# PCU.net
KiCad netlist of a schematic drawn in EAGLE
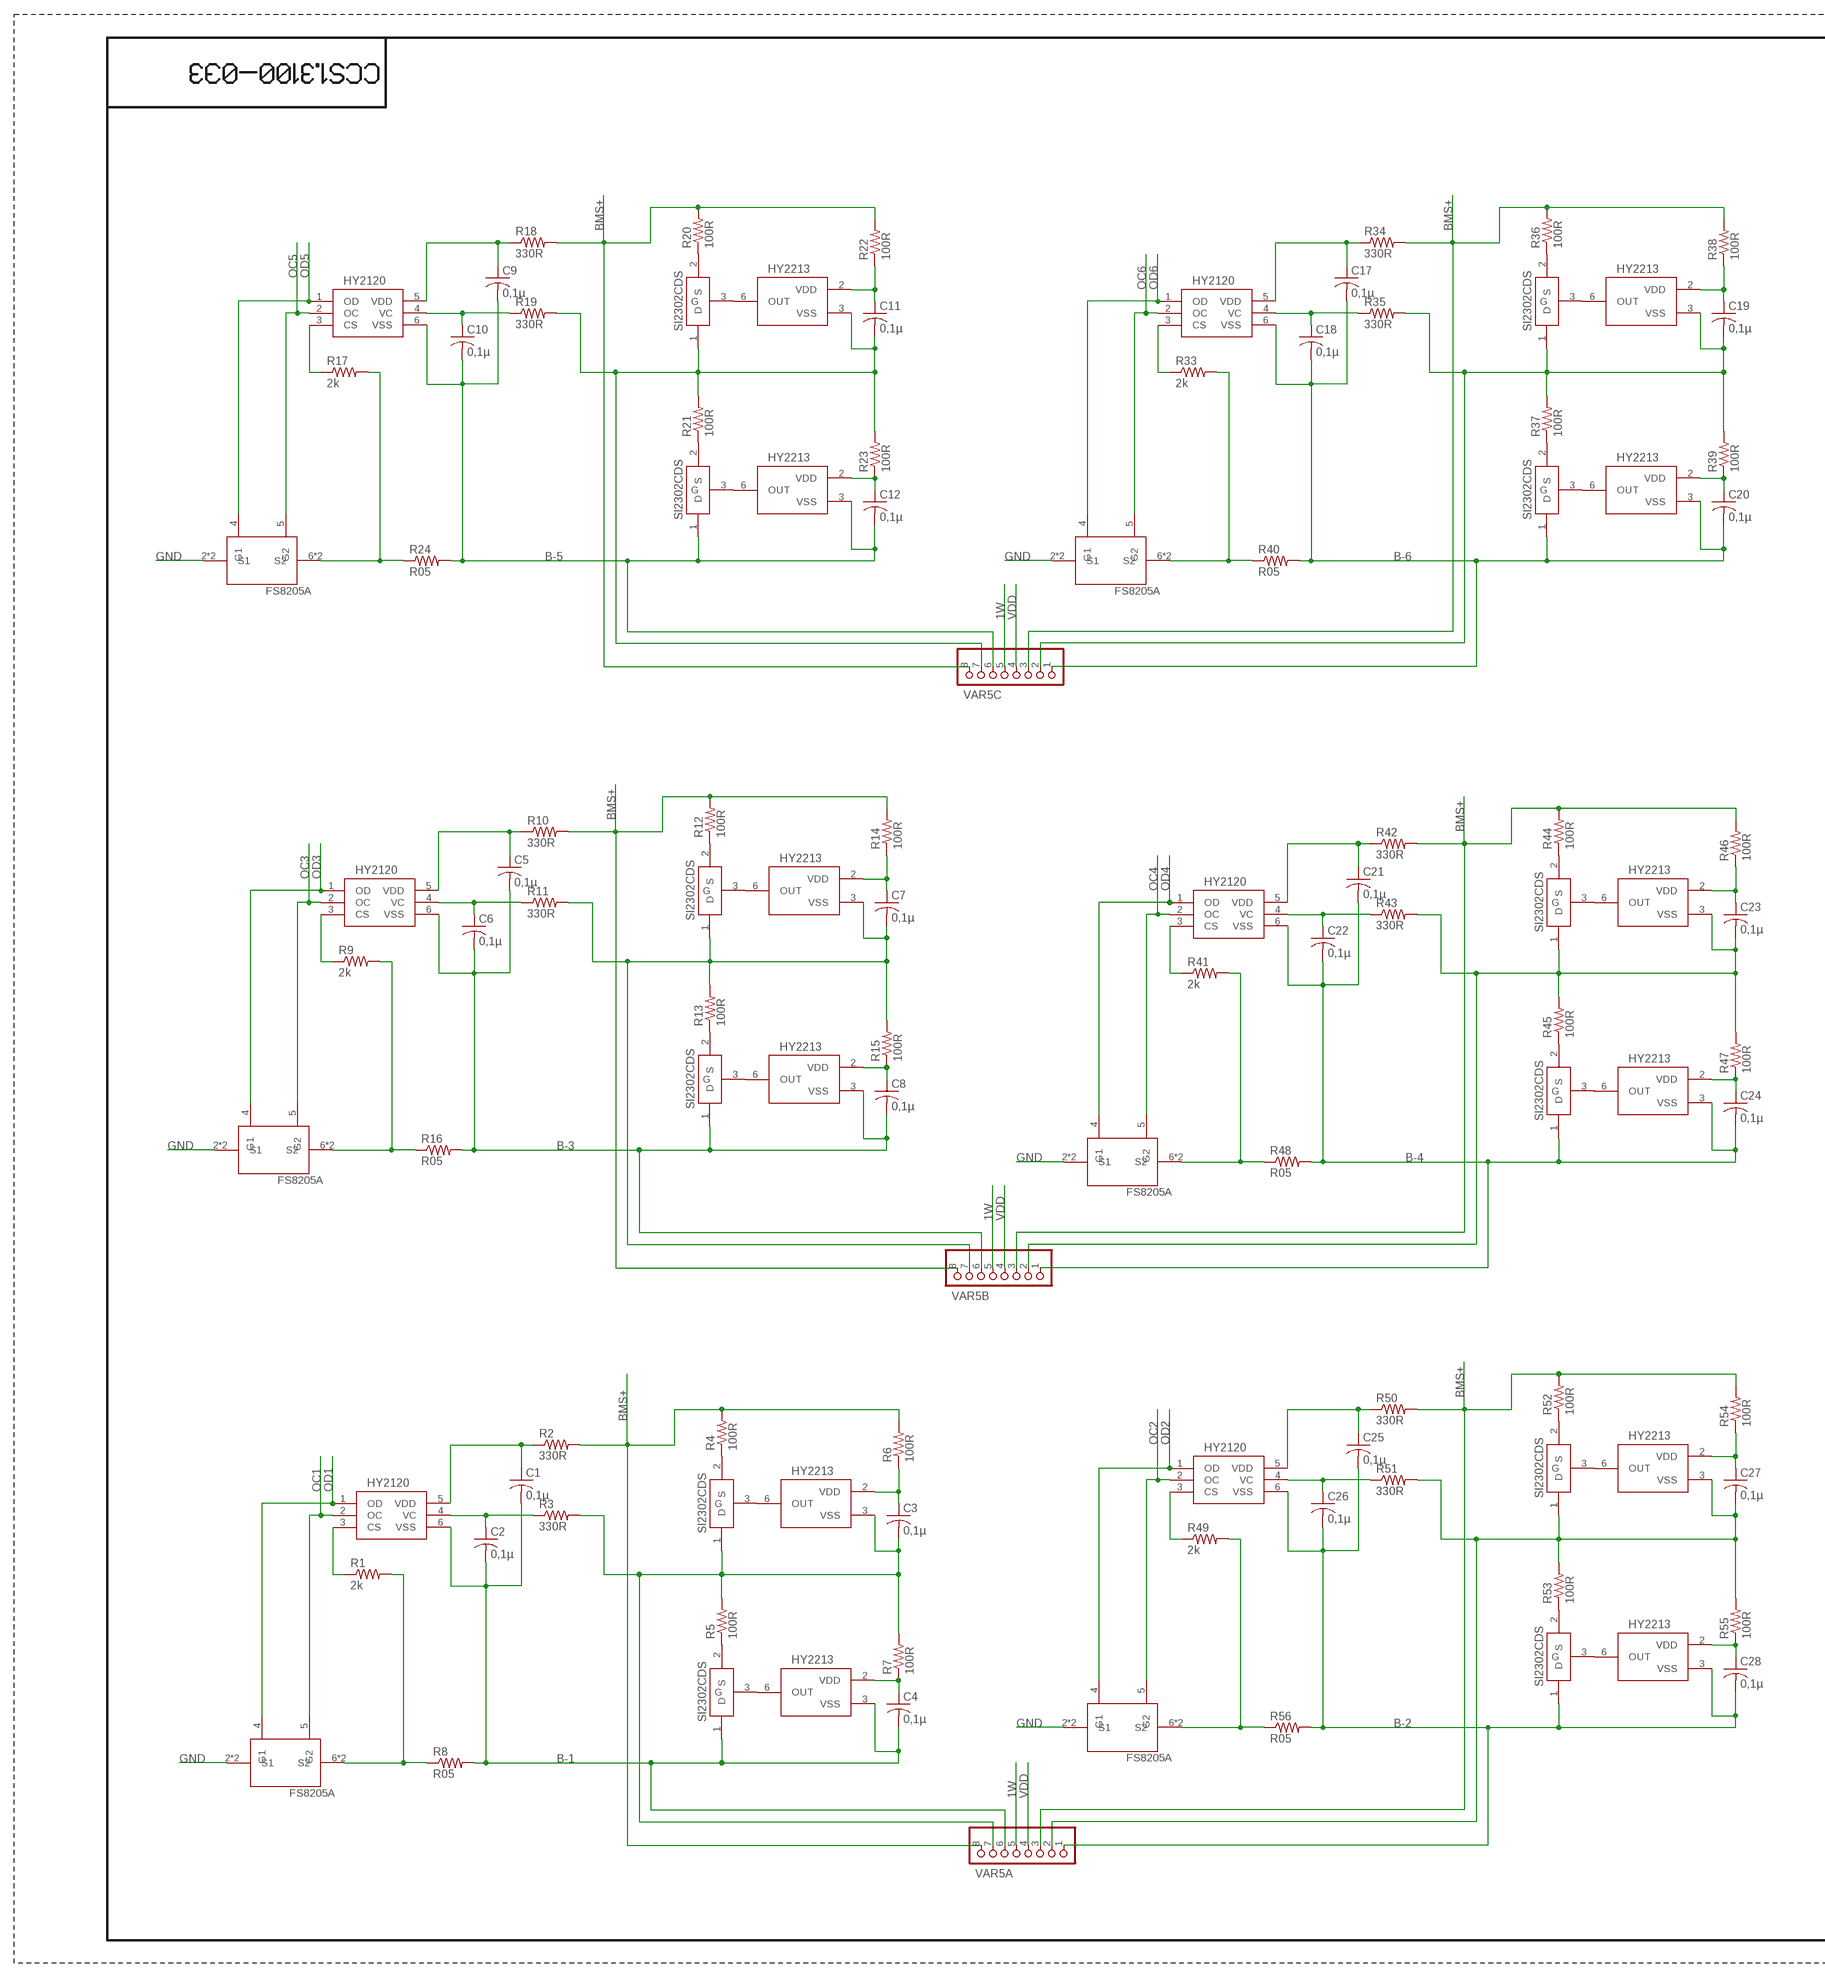
[diagram p0: schematic, sheet 1, part 1 of 2]
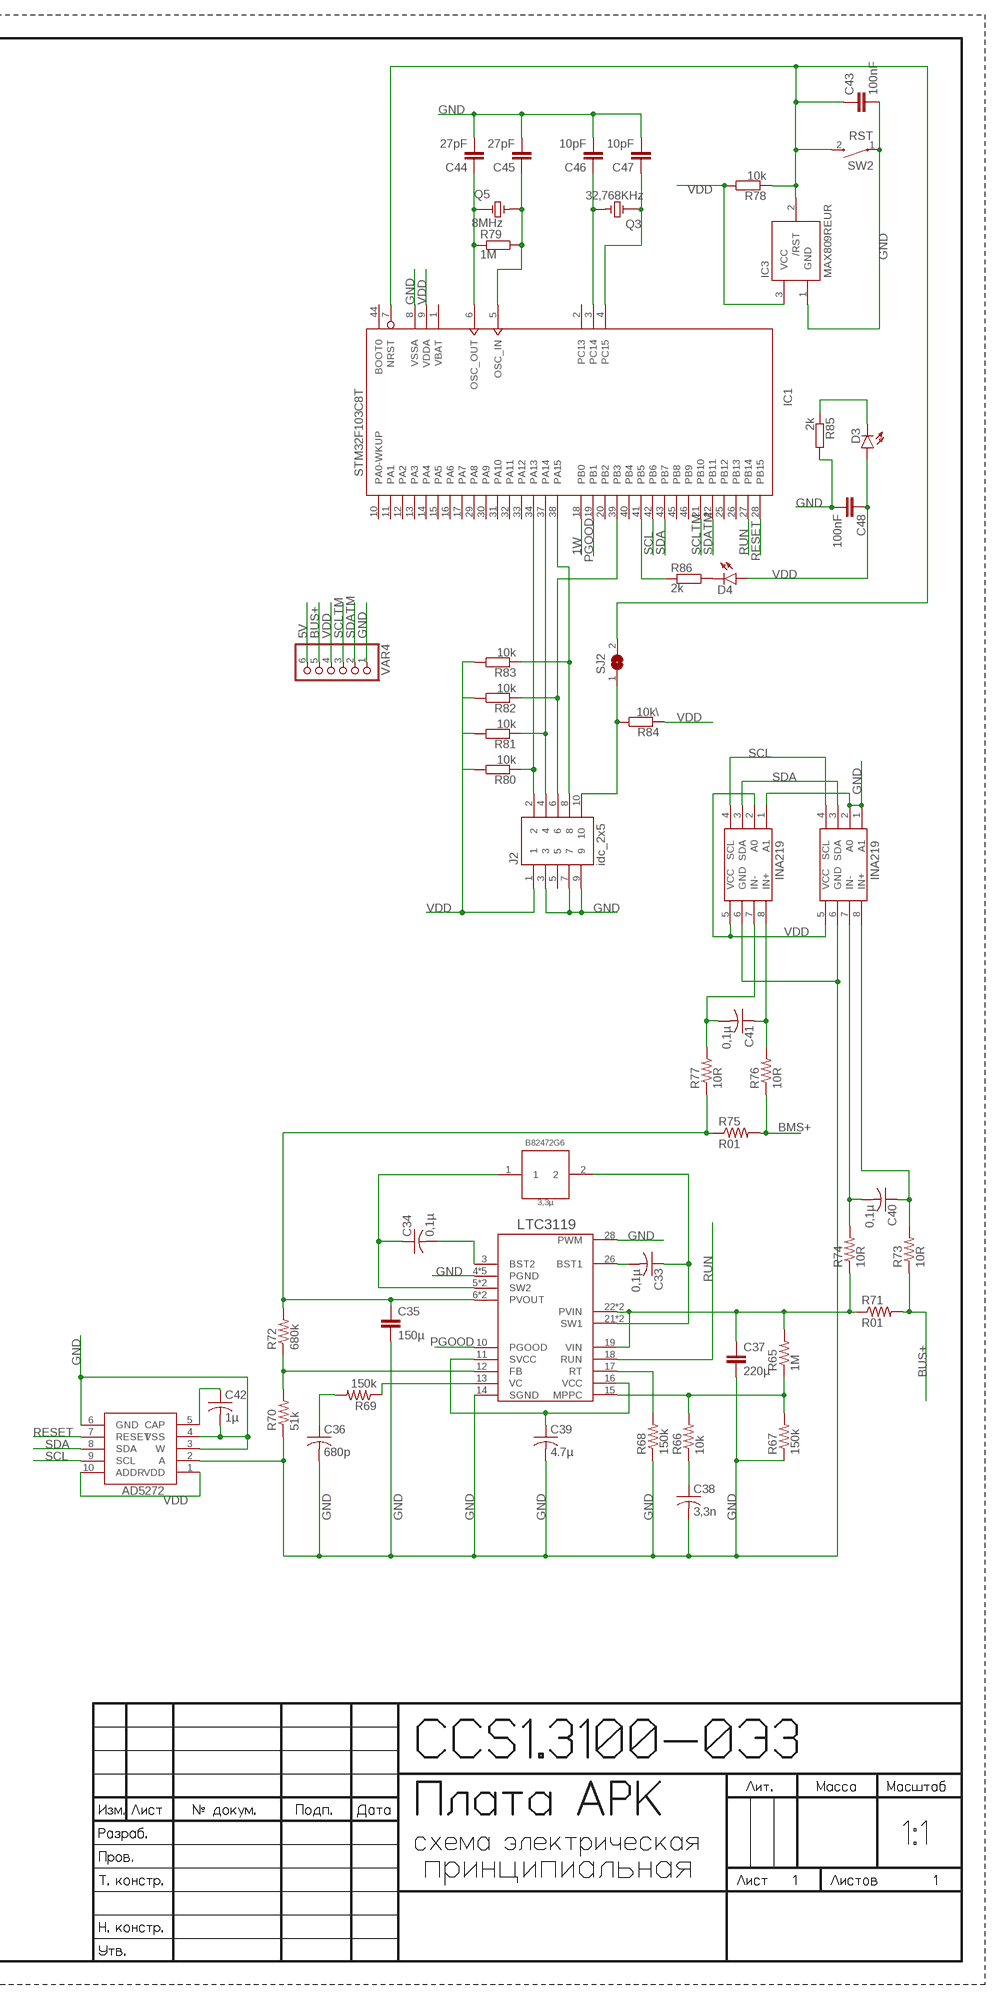
[diagram p1: schematic, sheet 1, part 2 of 2]

(export (version "E")
  (design (tool "Eeschema 10.0.6"))
  (components
    (comp (ref "3,3µH")
      (value "3,3µ")
      (footprint "eagle-import:B82472G6")
      (libsource (lib "eagle-import") (part "B82472G6"))
    )
    (comp (ref "C1")
      (value "0,1µ")
      (footprint "eagle-import:C0603")
      (libsource (lib "eagle-import") (part "C-USC0603"))
    )
    (comp (ref "C2")
      (value "0,1µ")
      (footprint "eagle-import:C0603")
      (libsource (lib "eagle-import") (part "C-USC0603"))
    )
    (comp (ref "C3")
      (value "0,1µ")
      (footprint "eagle-import:C0603")
      (libsource (lib "eagle-import") (part "C-USC0603"))
    )
    (comp (ref "C4")
      (value "0,1µ")
      (footprint "eagle-import:C0603")
      (libsource (lib "eagle-import") (part "C-USC0603"))
    )
    (comp (ref "C5")
      (value "0,1µ")
      (footprint "eagle-import:C0603")
      (libsource (lib "eagle-import") (part "C-USC0603"))
    )
    (comp (ref "C6")
      (value "0,1µ")
      (footprint "eagle-import:C0603")
      (libsource (lib "eagle-import") (part "C-USC0603"))
    )
    (comp (ref "C7")
      (value "0,1µ")
      (footprint "eagle-import:C0603")
      (libsource (lib "eagle-import") (part "C-USC0603"))
    )
    (comp (ref "C8")
      (value "0,1µ")
      (footprint "eagle-import:C0603")
      (libsource (lib "eagle-import") (part "C-USC0603"))
    )
    (comp (ref "C9")
      (value "0,1µ")
      (footprint "eagle-import:C0603")
      (libsource (lib "eagle-import") (part "C-USC0603"))
    )
    (comp (ref "C10")
      (value "0,1µ")
      (footprint "eagle-import:C0603")
      (libsource (lib "eagle-import") (part "C-USC0603"))
    )
    (comp (ref "C11")
      (value "0,1µ")
      (footprint "eagle-import:C0603")
      (libsource (lib "eagle-import") (part "C-USC0603"))
    )
    (comp (ref "C12")
      (value "0,1µ")
      (footprint "eagle-import:C0603")
      (libsource (lib "eagle-import") (part "C-USC0603"))
    )
    (comp (ref "C17")
      (value "0,1µ")
      (footprint "eagle-import:C0603")
      (libsource (lib "eagle-import") (part "C-USC0603"))
    )
    (comp (ref "C18")
      (value "0,1µ")
      (footprint "eagle-import:C0603")
      (libsource (lib "eagle-import") (part "C-USC0603"))
    )
    (comp (ref "C19")
      (value "0,1µ")
      (footprint "eagle-import:C0603")
      (libsource (lib "eagle-import") (part "C-USC0603"))
    )
    (comp (ref "C20")
      (value "0,1µ")
      (footprint "eagle-import:C0603")
      (libsource (lib "eagle-import") (part "C-USC0603"))
    )
    (comp (ref "C21")
      (value "0,1µ")
      (footprint "eagle-import:C0603")
      (libsource (lib "eagle-import") (part "C-USC0603"))
    )
    (comp (ref "C22")
      (value "0,1µ")
      (footprint "eagle-import:C0603")
      (libsource (lib "eagle-import") (part "C-USC0603"))
    )
    (comp (ref "C23")
      (value "0,1µ")
      (footprint "eagle-import:C0603")
      (libsource (lib "eagle-import") (part "C-USC0603"))
    )
    (comp (ref "C24")
      (value "0,1µ")
      (footprint "eagle-import:C0603")
      (libsource (lib "eagle-import") (part "C-USC0603"))
    )
    (comp (ref "C25")
      (value "0,1µ")
      (footprint "eagle-import:C0603")
      (libsource (lib "eagle-import") (part "C-USC0603"))
    )
    (comp (ref "C26")
      (value "0,1µ")
      (footprint "eagle-import:C0603")
      (libsource (lib "eagle-import") (part "C-USC0603"))
    )
    (comp (ref "C27")
      (value "0,1µ")
      (footprint "eagle-import:C0603")
      (libsource (lib "eagle-import") (part "C-USC0603"))
    )
    (comp (ref "C28")
      (value "0,1µ")
      (footprint "eagle-import:C0603")
      (libsource (lib "eagle-import") (part "C-USC0603"))
    )
    (comp (ref "C33")
      (value "0,1µ")
      (footprint "eagle-import:C0603")
      (libsource (lib "eagle-import") (part "C-USC0603"))
    )
    (comp (ref "C34")
      (value "0,1µ")
      (footprint "eagle-import:C0603")
      (libsource (lib "eagle-import") (part "C-USC0603"))
    )
    (comp (ref "C35")
      (value "150µ")
      (footprint "eagle-import:ECAP150")
      (libsource (lib "eagle-import") (part "ECAPECAP150"))
    )
    (comp (ref "C36")
      (value "680p")
      (footprint "eagle-import:C1206")
      (libsource (lib "eagle-import") (part "C-USC1206"))
    )
    (comp (ref "C37")
      (value "220µ")
      (footprint "eagle-import:ECAP220")
      (libsource (lib "eagle-import") (part "ECAPECAP220"))
    )
    (comp (ref "C38")
      (value "3,3n")
      (footprint "eagle-import:C1206")
      (libsource (lib "eagle-import") (part "C-USC1206"))
    )
    (comp (ref "C39")
      (value "4.7µ")
      (footprint "eagle-import:C1206")
      (libsource (lib "eagle-import") (part "C-USC1206"))
    )
    (comp (ref "C40")
      (value "0,1µ")
      (footprint "eagle-import:C0603")
      (libsource (lib "eagle-import") (part "C-USC0603"))
    )
    (comp (ref "C41")
      (value "0,1µ")
      (footprint "eagle-import:C0603")
      (libsource (lib "eagle-import") (part "C-USC0603"))
    )
    (comp (ref "C42")
      (value "1µ")
      (footprint "eagle-import:C0603")
      (libsource (lib "eagle-import") (part "C-USC0603"))
    )
    (comp (ref "C43")
      (value "100nF")
      (footprint "eagle-import:C0603")
      (libsource (lib "eagle-import") (part "C-EUC0603"))
    )
    (comp (ref "C44")
      (value "27pF")
      (footprint "eagle-import:C0603")
      (libsource (lib "eagle-import") (part "C-EUC0603"))
    )
    (comp (ref "C45")
      (value "27pF")
      (footprint "eagle-import:C0603")
      (libsource (lib "eagle-import") (part "C-EUC0603"))
    )
    (comp (ref "C46")
      (value "10pF")
      (footprint "eagle-import:C0603")
      (libsource (lib "eagle-import") (part "C-EUC0603"))
    )
    (comp (ref "C47")
      (value "10pF")
      (footprint "eagle-import:C0603")
      (libsource (lib "eagle-import") (part "C-EUC0603"))
    )
    (comp (ref "C48")
      (value "100nF")
      (footprint "eagle-import:C0603")
      (libsource (lib "eagle-import") (part "C-EUC0603"))
    )
    (comp (ref "D3")
      (value "HLMP6")
      (footprint "eagle-import:HLMP6")
      (fields (field (name "MF") "AGILENT TECHNOLOGIES") (field (name "MPN") "HLMP-6500"))
      (libsource (lib "eagle-import") (part "HLMP6"))
    )
    (comp (ref "D4")
      (value "HLMP6")
      (footprint "eagle-import:HLMP6")
      (fields (field (name "MF") "AGILENT TECHNOLOGIES") (field (name "MPN") "HLMP-6500"))
      (libsource (lib "eagle-import") (part "HLMP6"))
    )
    (comp (ref "IC1")
      (value "STM32F103C8T")
      (footprint "eagle-import:LQFP48")
      (libsource (lib "eagle-import") (part "STM32F103CT8"))
    )
    (comp (ref "IC3")
      (value "MAX809REUR")
      (footprint "eagle-import:SOT23")
      (fields (field (name "MF") "ON Semiconductor") (field (name "MP") "MAX809"))
      (libsource (lib "eagle-import") (part "MAX809EUR"))
    )
    (comp (ref "J2")
      (value "idc_2x5")
      (footprint "eagle-import:CNC_3221-10-0100-00")
      (fields (field (name "MF") "CNC Tech") (field (name "MP") "3221-10-0100-00"))
      (libsource (lib "eagle-import") (part "3221-10-0100-00"))
    )
    (comp (ref "Q3")
      (value "32,768KHz")
      (footprint "eagle-import:XTAL_9C-8.000MEEJ-T")
      (fields (field (name "MF") "TXC CORPORATION") (field (name "MP") "9C-8.000MEEJ-T"))
      (libsource (lib "eagle-import") (part "9C-8.000MEEJ-T"))
    )
    (comp (ref "Q5")
      (value "8MHz")
      (footprint "eagle-import:XTAL_9C-8.000MEEJ-T")
      (fields (field (name "MF") "TXC CORPORATION") (field (name "MP") "9C-8.000MEEJ-T"))
      (libsource (lib "eagle-import") (part "9C-8.000MEEJ-T"))
    )
    (comp (ref "R1")
      (value "2k")
      (footprint "eagle-import:R0603")
      (libsource (lib "eagle-import") (part "resistor_348_R-US_R0603"))
    )
    (comp (ref "R2")
      (value "330R")
      (footprint "eagle-import:R0603")
      (libsource (lib "eagle-import") (part "resistor_348_R-US_R0603"))
    )
    (comp (ref "R3")
      (value "330R")
      (footprint "eagle-import:R0603")
      (libsource (lib "eagle-import") (part "resistor_348_R-US_R0603"))
    )
    (comp (ref "R4")
      (value "100R")
      (footprint "eagle-import:R0603")
      (libsource (lib "eagle-import") (part "resistor_348_R-US_R0603"))
    )
    (comp (ref "R5")
      (value "100R")
      (footprint "eagle-import:R0603")
      (libsource (lib "eagle-import") (part "resistor_348_R-US_R0603"))
    )
    (comp (ref "R6")
      (value "100R")
      (footprint "eagle-import:R0603")
      (libsource (lib "eagle-import") (part "resistor_348_R-US_R0603"))
    )
    (comp (ref "R7")
      (value "100R")
      (footprint "eagle-import:R0603")
      (libsource (lib "eagle-import") (part "resistor_348_R-US_R0603"))
    )
    (comp (ref "R8")
      (value "R05")
      (footprint "eagle-import:R2512")
      (libsource (lib "eagle-import") (part "R-US_R2512"))
    )
    (comp (ref "R9")
      (value "2k")
      (footprint "eagle-import:R0603")
      (libsource (lib "eagle-import") (part "resistor_348_R-US_R0603"))
    )
    (comp (ref "R10")
      (value "330R")
      (footprint "eagle-import:R0603")
      (libsource (lib "eagle-import") (part "resistor_348_R-US_R0603"))
    )
    (comp (ref "R11")
      (value "330R")
      (footprint "eagle-import:R0603")
      (libsource (lib "eagle-import") (part "resistor_348_R-US_R0603"))
    )
    (comp (ref "R12")
      (value "100R")
      (footprint "eagle-import:R0603")
      (libsource (lib "eagle-import") (part "resistor_348_R-US_R0603"))
    )
    (comp (ref "R13")
      (value "100R")
      (footprint "eagle-import:R0603")
      (libsource (lib "eagle-import") (part "resistor_348_R-US_R0603"))
    )
    (comp (ref "R14")
      (value "100R")
      (footprint "eagle-import:R0603")
      (libsource (lib "eagle-import") (part "resistor_348_R-US_R0603"))
    )
    (comp (ref "R15")
      (value "100R")
      (footprint "eagle-import:R0603")
      (libsource (lib "eagle-import") (part "resistor_348_R-US_R0603"))
    )
    (comp (ref "R16")
      (value "R05")
      (footprint "eagle-import:R2512")
      (libsource (lib "eagle-import") (part "R-US_R2512"))
    )
    (comp (ref "R17")
      (value "2k")
      (footprint "eagle-import:R0603")
      (libsource (lib "eagle-import") (part "resistor_348_R-US_R0603"))
    )
    (comp (ref "R18")
      (value "330R")
      (footprint "eagle-import:R0603")
      (libsource (lib "eagle-import") (part "resistor_348_R-US_R0603"))
    )
    (comp (ref "R19")
      (value "330R")
      (footprint "eagle-import:R0603")
      (libsource (lib "eagle-import") (part "resistor_348_R-US_R0603"))
    )
    (comp (ref "R20")
      (value "100R")
      (footprint "eagle-import:R0603")
      (libsource (lib "eagle-import") (part "resistor_348_R-US_R0603"))
    )
    (comp (ref "R21")
      (value "100R")
      (footprint "eagle-import:R0603")
      (libsource (lib "eagle-import") (part "resistor_348_R-US_R0603"))
    )
    (comp (ref "R22")
      (value "100R")
      (footprint "eagle-import:R0603")
      (libsource (lib "eagle-import") (part "resistor_348_R-US_R0603"))
    )
    (comp (ref "R23")
      (value "100R")
      (footprint "eagle-import:R0603")
      (libsource (lib "eagle-import") (part "resistor_348_R-US_R0603"))
    )
    (comp (ref "R24")
      (value "R05")
      (footprint "eagle-import:R2512")
      (libsource (lib "eagle-import") (part "R-US_R2512"))
    )
    (comp (ref "R33")
      (value "2k")
      (footprint "eagle-import:R0603")
      (libsource (lib "eagle-import") (part "resistor_348_R-US_R0603"))
    )
    (comp (ref "R34")
      (value "330R")
      (footprint "eagle-import:R0603")
      (libsource (lib "eagle-import") (part "resistor_348_R-US_R0603"))
    )
    (comp (ref "R35")
      (value "330R")
      (footprint "eagle-import:R0603")
      (libsource (lib "eagle-import") (part "resistor_348_R-US_R0603"))
    )
    (comp (ref "R36")
      (value "100R")
      (footprint "eagle-import:R0603")
      (libsource (lib "eagle-import") (part "resistor_348_R-US_R0603"))
    )
    (comp (ref "R37")
      (value "100R")
      (footprint "eagle-import:R0603")
      (libsource (lib "eagle-import") (part "resistor_348_R-US_R0603"))
    )
    (comp (ref "R38")
      (value "100R")
      (footprint "eagle-import:R0603")
      (libsource (lib "eagle-import") (part "resistor_348_R-US_R0603"))
    )
    (comp (ref "R39")
      (value "100R")
      (footprint "eagle-import:R0603")
      (libsource (lib "eagle-import") (part "resistor_348_R-US_R0603"))
    )
    (comp (ref "R40")
      (value "R05")
      (footprint "eagle-import:R2512")
      (libsource (lib "eagle-import") (part "R-US_R2512"))
    )
    (comp (ref "R41")
      (value "2k")
      (footprint "eagle-import:R0603")
      (libsource (lib "eagle-import") (part "resistor_348_R-US_R0603"))
    )
    (comp (ref "R42")
      (value "330R")
      (footprint "eagle-import:R0603")
      (libsource (lib "eagle-import") (part "resistor_348_R-US_R0603"))
    )
    (comp (ref "R43")
      (value "330R")
      (footprint "eagle-import:R0603")
      (libsource (lib "eagle-import") (part "resistor_348_R-US_R0603"))
    )
    (comp (ref "R44")
      (value "100R")
      (footprint "eagle-import:R0603")
      (libsource (lib "eagle-import") (part "resistor_348_R-US_R0603"))
    )
    (comp (ref "R45")
      (value "100R")
      (footprint "eagle-import:R0603")
      (libsource (lib "eagle-import") (part "resistor_348_R-US_R0603"))
    )
    (comp (ref "R46")
      (value "100R")
      (footprint "eagle-import:R0603")
      (libsource (lib "eagle-import") (part "resistor_348_R-US_R0603"))
    )
    (comp (ref "R47")
      (value "100R")
      (footprint "eagle-import:R0603")
      (libsource (lib "eagle-import") (part "resistor_348_R-US_R0603"))
    )
    (comp (ref "R48")
      (value "R05")
      (footprint "eagle-import:R2512")
      (libsource (lib "eagle-import") (part "R-US_R2512"))
    )
    (comp (ref "R49")
      (value "2k")
      (footprint "eagle-import:R0603")
      (libsource (lib "eagle-import") (part "resistor_348_R-US_R0603"))
    )
    (comp (ref "R50")
      (value "330R")
      (footprint "eagle-import:R0603")
      (libsource (lib "eagle-import") (part "resistor_348_R-US_R0603"))
    )
    (comp (ref "R51")
      (value "330R")
      (footprint "eagle-import:R0603")
      (libsource (lib "eagle-import") (part "resistor_348_R-US_R0603"))
    )
    (comp (ref "R52")
      (value "100R")
      (footprint "eagle-import:R0603")
      (libsource (lib "eagle-import") (part "resistor_348_R-US_R0603"))
    )
    (comp (ref "R53")
      (value "100R")
      (footprint "eagle-import:R0603")
      (libsource (lib "eagle-import") (part "resistor_348_R-US_R0603"))
    )
    (comp (ref "R54")
      (value "100R")
      (footprint "eagle-import:R0603")
      (libsource (lib "eagle-import") (part "resistor_348_R-US_R0603"))
    )
    (comp (ref "R55")
      (value "100R")
      (footprint "eagle-import:R0603")
      (libsource (lib "eagle-import") (part "resistor_348_R-US_R0603"))
    )
    (comp (ref "R56")
      (value "R05")
      (footprint "eagle-import:R2512")
      (libsource (lib "eagle-import") (part "R-US_R2512"))
    )
    (comp (ref "R65")
      (value "1M")
      (footprint "eagle-import:R0603")
      (libsource (lib "eagle-import") (part "resistor_348_R-US_R0603"))
    )
    (comp (ref "R66")
      (value "10k")
      (footprint "eagle-import:R0603")
      (libsource (lib "eagle-import") (part "resistor_348_R-US_R0603"))
    )
    (comp (ref "R67")
      (value "150k")
      (footprint "eagle-import:R0603")
      (libsource (lib "eagle-import") (part "resistor_348_R-US_R0603"))
    )
    (comp (ref "R68")
      (value "150k")
      (footprint "eagle-import:R0603")
      (libsource (lib "eagle-import") (part "resistor_348_R-US_R0603"))
    )
    (comp (ref "R69")
      (value "150k")
      (footprint "eagle-import:R0603")
      (libsource (lib "eagle-import") (part "resistor_348_R-US_R0603"))
    )
    (comp (ref "R70")
      (value "51k")
      (footprint "eagle-import:R0603")
      (libsource (lib "eagle-import") (part "resistor_348_R-US_R0603"))
    )
    (comp (ref "R71")
      (value "R01")
      (footprint "eagle-import:R2512")
      (libsource (lib "eagle-import") (part "R-US_R2512"))
    )
    (comp (ref "R72")
      (value "680k")
      (footprint "eagle-import:R0603")
      (libsource (lib "eagle-import") (part "resistor_348_R-US_R0603"))
    )
    (comp (ref "R73")
      (value "10R")
      (footprint "eagle-import:R0603")
      (libsource (lib "eagle-import") (part "resistor_348_R-US_R0603"))
    )
    (comp (ref "R74")
      (value "10R")
      (footprint "eagle-import:R0603")
      (libsource (lib "eagle-import") (part "resistor_348_R-US_R0603"))
    )
    (comp (ref "R75")
      (value "R01")
      (footprint "eagle-import:R2512")
      (libsource (lib "eagle-import") (part "R-US_R2512"))
    )
    (comp (ref "R76")
      (value "10R")
      (footprint "eagle-import:R0603")
      (libsource (lib "eagle-import") (part "resistor_348_R-US_R0603"))
    )
    (comp (ref "R77")
      (value "10R")
      (footprint "eagle-import:R0603")
      (libsource (lib "eagle-import") (part "resistor_348_R-US_R0603"))
    )
    (comp (ref "R78")
      (value "10k")
      (footprint "eagle-import:BVS")
      (libsource (lib "eagle-import") (part "BVS"))
    )
    (comp (ref "R79")
      (value "1M")
      (footprint "eagle-import:BVS")
      (libsource (lib "eagle-import") (part "BVS"))
    )
    (comp (ref "R80")
      (value "10k")
      (footprint "eagle-import:BVS")
      (libsource (lib "eagle-import") (part "BVS"))
    )
    (comp (ref "R81")
      (value "10k")
      (footprint "eagle-import:BVS")
      (libsource (lib "eagle-import") (part "BVS"))
    )
    (comp (ref "R82")
      (value "10k")
      (footprint "eagle-import:BVS")
      (libsource (lib "eagle-import") (part "BVS"))
    )
    (comp (ref "R83")
      (value "10k")
      (footprint "eagle-import:BVS")
      (libsource (lib "eagle-import") (part "BVS"))
    )
    (comp (ref "R84")
      (value "10k\\")
      (footprint "eagle-import:BVS")
      (libsource (lib "eagle-import") (part "BVS"))
    )
    (comp (ref "R85")
      (value "2k")
      (footprint "eagle-import:BVS")
      (libsource (lib "eagle-import") (part "BVS"))
    )
    (comp (ref "R86")
      (value "2k")
      (footprint "eagle-import:BVS")
      (libsource (lib "eagle-import") (part "BVS"))
    )
    (comp (ref "SJ2")
      (value "SJW")
      (footprint "eagle-import:SJW")
      (libsource (lib "eagle-import") (part "SJW"))
    )
    (comp (ref "SW2")
      (value "RST")
      (footprint "eagle-import:SW_1437566-3")
      (fields (field (name "COMMENT") "1437566-3") (field (name "MF") "TE Connectivity"))
      (libsource (lib "eagle-import") (part "1437566-3"))
    )
    (comp (ref "U$1")
      (value "FS8205A")
      (footprint "eagle-import:FS8205A")
      (libsource (lib "eagle-import") (part "FS8205A"))
    )
    (comp (ref "U$3")
      (value "HY2120")
      (footprint "eagle-import:HY2120")
      (libsource (lib "eagle-import") (part "HY2120"))
    )
    (comp (ref "U$4")
      (value "HY2213")
      (footprint "eagle-import:HY2213")
      (libsource (lib "eagle-import") (part "HY2213"))
    )
    (comp (ref "U$5")
      (value "HY2213")
      (footprint "eagle-import:HY2213")
      (libsource (lib "eagle-import") (part "HY2213"))
    )
    (comp (ref "U$6")
      (value "SI2302CDS")
      (footprint "eagle-import:SI2302CDS")
      (libsource (lib "eagle-import") (part "SI2302CDS"))
    )
    (comp (ref "U$7")
      (value "SI2302CDS")
      (footprint "eagle-import:SI2302CDS")
      (libsource (lib "eagle-import") (part "SI2302CDS"))
    )
    (comp (ref "U$8")
      (value "FS8205A")
      (footprint "eagle-import:FS8205A")
      (libsource (lib "eagle-import") (part "FS8205A"))
    )
    (comp (ref "U$10")
      (value "HY2120")
      (footprint "eagle-import:HY2120")
      (libsource (lib "eagle-import") (part "HY2120"))
    )
    (comp (ref "U$11")
      (value "HY2213")
      (footprint "eagle-import:HY2213")
      (libsource (lib "eagle-import") (part "HY2213"))
    )
    (comp (ref "U$12")
      (value "HY2213")
      (footprint "eagle-import:HY2213")
      (libsource (lib "eagle-import") (part "HY2213"))
    )
    (comp (ref "U$13")
      (value "SI2302CDS")
      (footprint "eagle-import:SI2302CDS")
      (libsource (lib "eagle-import") (part "SI2302CDS"))
    )
    (comp (ref "U$14")
      (value "SI2302CDS")
      (footprint "eagle-import:SI2302CDS")
      (libsource (lib "eagle-import") (part "SI2302CDS"))
    )
    (comp (ref "U$15")
      (value "FS8205A")
      (footprint "eagle-import:FS8205A")
      (libsource (lib "eagle-import") (part "FS8205A"))
    )
    (comp (ref "U$17")
      (value "HY2120")
      (footprint "eagle-import:HY2120")
      (libsource (lib "eagle-import") (part "HY2120"))
    )
    (comp (ref "U$18")
      (value "HY2213")
      (footprint "eagle-import:HY2213")
      (libsource (lib "eagle-import") (part "HY2213"))
    )
    (comp (ref "U$19")
      (value "HY2213")
      (footprint "eagle-import:HY2213")
      (libsource (lib "eagle-import") (part "HY2213"))
    )
    (comp (ref "U$20")
      (value "SI2302CDS")
      (footprint "eagle-import:SI2302CDS")
      (libsource (lib "eagle-import") (part "SI2302CDS"))
    )
    (comp (ref "U$21")
      (value "SI2302CDS")
      (footprint "eagle-import:SI2302CDS")
      (libsource (lib "eagle-import") (part "SI2302CDS"))
    )
    (comp (ref "U$29")
      (value "FS8205A")
      (footprint "eagle-import:FS8205A")
      (libsource (lib "eagle-import") (part "FS8205A"))
    )
    (comp (ref "U$31")
      (value "HY2120")
      (footprint "eagle-import:HY2120")
      (libsource (lib "eagle-import") (part "HY2120"))
    )
    (comp (ref "U$32")
      (value "HY2213")
      (footprint "eagle-import:HY2213")
      (libsource (lib "eagle-import") (part "HY2213"))
    )
    (comp (ref "U$33")
      (value "HY2213")
      (footprint "eagle-import:HY2213")
      (libsource (lib "eagle-import") (part "HY2213"))
    )
    (comp (ref "U$34")
      (value "SI2302CDS")
      (footprint "eagle-import:SI2302CDS")
      (libsource (lib "eagle-import") (part "SI2302CDS"))
    )
    (comp (ref "U$35")
      (value "SI2302CDS")
      (footprint "eagle-import:SI2302CDS")
      (libsource (lib "eagle-import") (part "SI2302CDS"))
    )
    (comp (ref "U$36")
      (value "FS8205A")
      (footprint "eagle-import:FS8205A")
      (libsource (lib "eagle-import") (part "FS8205A"))
    )
    (comp (ref "U$38")
      (value "HY2120")
      (footprint "eagle-import:HY2120")
      (libsource (lib "eagle-import") (part "HY2120"))
    )
    (comp (ref "U$39")
      (value "HY2213")
      (footprint "eagle-import:HY2213")
      (libsource (lib "eagle-import") (part "HY2213"))
    )
    (comp (ref "U$40")
      (value "HY2213")
      (footprint "eagle-import:HY2213")
      (libsource (lib "eagle-import") (part "HY2213"))
    )
    (comp (ref "U$41")
      (value "SI2302CDS")
      (footprint "eagle-import:SI2302CDS")
      (libsource (lib "eagle-import") (part "SI2302CDS"))
    )
    (comp (ref "U$42")
      (value "SI2302CDS")
      (footprint "eagle-import:SI2302CDS")
      (libsource (lib "eagle-import") (part "SI2302CDS"))
    )
    (comp (ref "U$43")
      (value "FS8205A")
      (footprint "eagle-import:FS8205A")
      (libsource (lib "eagle-import") (part "FS8205A"))
    )
    (comp (ref "U$45")
      (value "HY2120")
      (footprint "eagle-import:HY2120")
      (libsource (lib "eagle-import") (part "HY2120"))
    )
    (comp (ref "U$46")
      (value "HY2213")
      (footprint "eagle-import:HY2213")
      (libsource (lib "eagle-import") (part "HY2213"))
    )
    (comp (ref "U$47")
      (value "HY2213")
      (footprint "eagle-import:HY2213")
      (libsource (lib "eagle-import") (part "HY2213"))
    )
    (comp (ref "U$48")
      (value "SI2302CDS")
      (footprint "eagle-import:SI2302CDS")
      (libsource (lib "eagle-import") (part "SI2302CDS"))
    )
    (comp (ref "U$49")
      (value "SI2302CDS")
      (footprint "eagle-import:SI2302CDS")
      (libsource (lib "eagle-import") (part "SI2302CDS"))
    )
    (comp (ref "U$57")
      (value "INA219AID")
      (footprint "eagle-import:INA219AID")
      (libsource (lib "eagle-import") (part "INA219AID"))
    )
    (comp (ref "U$58")
      (value "INA219AID")
      (footprint "eagle-import:INA219AID")
      (libsource (lib "eagle-import") (part "INA219AID"))
    )
    (comp (ref "U$59")
      (value "LTC3119")
      (footprint "eagle-import:LTC3119")
      (libsource (lib "eagle-import") (part "LTC3119"))
    )
    (comp (ref "U$60")
      (value "AD5272")
      (footprint "eagle-import:AD5272")
      (libsource (lib "eagle-import") (part "AD5272"))
    )
    (comp (ref "VAR4")
      (value "PINHD-1X6")
      (footprint "eagle-import:1X06")
      (libsource (lib "eagle-import") (part "PINHD-1X6"))
    )
    (comp (ref "VAR5A")
      (value "PINHD-1X8")
      (footprint "eagle-import:1X08")
      (libsource (lib "eagle-import") (part "PINHD-1X8"))
    )
    (comp (ref "VAR5B")
      (value "PINHD-1X8")
      (footprint "eagle-import:1X08")
      (libsource (lib "eagle-import") (part "PINHD-1X8"))
    )
    (comp (ref "VAR5C")
      (value "PINHD-1X8")
      (footprint "eagle-import:1X08")
      (libsource (lib "eagle-import") (part "PINHD-1X8"))
    )
  )
  (nets
    (net (code "1") (name "/1W") (class "Default")
      (node (ref "IC1") (pin "18") (pinfunction "PB0_18") (pintype "bidirectional"))
      (node (ref "VAR5A") (pin "5") (pinfunction "5_5") (pintype "passive"))
      (node (ref "VAR5B") (pin "5") (pinfunction "5_5") (pintype "passive"))
      (node (ref "VAR5C") (pin "5") (pinfunction "5_5") (pintype "passive"))
    )
    (net (code "2") (name "/5V") (class "Default")
      (node (ref "VAR4") (pin "6") (pinfunction "6_6") (pintype "passive"))
    )
    (net (code "3") (name "/B-1") (class "Default")
      (node (ref "C1") (pin "2") (pinfunction "2_2") (pintype "passive"))
      (node (ref "C2") (pin "2") (pinfunction "2_2") (pintype "passive"))
      (node (ref "C4") (pin "2") (pinfunction "2_2") (pintype "passive"))
      (node (ref "R8") (pin "2") (pinfunction "2_2") (pintype "passive"))
      (node (ref "U$3") (pin "6") (pinfunction "VSS_6") (pintype "bidirectional"))
      (node (ref "U$5") (pin "3") (pinfunction "VSS_3") (pintype "bidirectional"))
      (node (ref "U$7") (pin "1") (pinfunction "D_1") (pintype "bidirectional"))
      (node (ref "VAR5A") (pin "6") (pinfunction "6_6") (pintype "passive"))
    )
    (net (code "4") (name "/B-2") (class "Default")
      (node (ref "C25") (pin "2") (pinfunction "2_2") (pintype "passive"))
      (node (ref "C26") (pin "2") (pinfunction "2_2") (pintype "passive"))
      (node (ref "C28") (pin "2") (pinfunction "2_2") (pintype "passive"))
      (node (ref "R56") (pin "2") (pinfunction "2_2") (pintype "passive"))
      (node (ref "U$45") (pin "6") (pinfunction "VSS_6") (pintype "bidirectional"))
      (node (ref "U$47") (pin "3") (pinfunction "VSS_3") (pintype "bidirectional"))
      (node (ref "U$49") (pin "1") (pinfunction "D_1") (pintype "bidirectional"))
      (node (ref "VAR5A") (pin "1") (pinfunction "1_1") (pintype "passive"))
    )
    (net (code "5") (name "/B-3") (class "Default")
      (node (ref "C5") (pin "2") (pinfunction "2_2") (pintype "passive"))
      (node (ref "C6") (pin "2") (pinfunction "2_2") (pintype "passive"))
      (node (ref "C8") (pin "2") (pinfunction "2_2") (pintype "passive"))
      (node (ref "R16") (pin "2") (pinfunction "2_2") (pintype "passive"))
      (node (ref "U$10") (pin "6") (pinfunction "VSS_6") (pintype "bidirectional"))
      (node (ref "U$12") (pin "3") (pinfunction "VSS_3") (pintype "bidirectional"))
      (node (ref "U$14") (pin "1") (pinfunction "D_1") (pintype "bidirectional"))
      (node (ref "VAR5B") (pin "6") (pinfunction "6_6") (pintype "passive"))
    )
    (net (code "6") (name "/B-4") (class "Default")
      (node (ref "C21") (pin "2") (pinfunction "2_2") (pintype "passive"))
      (node (ref "C22") (pin "2") (pinfunction "2_2") (pintype "passive"))
      (node (ref "C24") (pin "2") (pinfunction "2_2") (pintype "passive"))
      (node (ref "R48") (pin "2") (pinfunction "2_2") (pintype "passive"))
      (node (ref "U$38") (pin "6") (pinfunction "VSS_6") (pintype "bidirectional"))
      (node (ref "U$40") (pin "3") (pinfunction "VSS_3") (pintype "bidirectional"))
      (node (ref "U$42") (pin "1") (pinfunction "D_1") (pintype "bidirectional"))
      (node (ref "VAR5B") (pin "1") (pinfunction "1_1") (pintype "passive"))
    )
    (net (code "7") (name "/B-5") (class "Default")
      (node (ref "C10") (pin "2") (pinfunction "2_2") (pintype "passive"))
      (node (ref "C12") (pin "2") (pinfunction "2_2") (pintype "passive"))
      (node (ref "C9") (pin "2") (pinfunction "2_2") (pintype "passive"))
      (node (ref "R24") (pin "2") (pinfunction "2_2") (pintype "passive"))
      (node (ref "U$17") (pin "6") (pinfunction "VSS_6") (pintype "bidirectional"))
      (node (ref "U$19") (pin "3") (pinfunction "VSS_3") (pintype "bidirectional"))
      (node (ref "U$21") (pin "1") (pinfunction "D_1") (pintype "bidirectional"))
      (node (ref "VAR5C") (pin "6") (pinfunction "6_6") (pintype "passive"))
    )
    (net (code "8") (name "/B-6") (class "Default")
      (node (ref "C17") (pin "2") (pinfunction "2_2") (pintype "passive"))
      (node (ref "C18") (pin "2") (pinfunction "2_2") (pintype "passive"))
      (node (ref "C20") (pin "2") (pinfunction "2_2") (pintype "passive"))
      (node (ref "R40") (pin "2") (pinfunction "2_2") (pintype "passive"))
      (node (ref "U$31") (pin "6") (pinfunction "VSS_6") (pintype "bidirectional"))
      (node (ref "U$33") (pin "3") (pinfunction "VSS_3") (pintype "bidirectional"))
      (node (ref "U$35") (pin "1") (pinfunction "D_1") (pintype "bidirectional"))
      (node (ref "VAR5C") (pin "1") (pinfunction "1_1") (pintype "passive"))
    )
    (net (code "9") (name "/BMS+") (class "Default")
      (node (ref "R10") (pin "2") (pinfunction "2_2") (pintype "passive"))
      (node (ref "R12") (pin "2") (pinfunction "2_2") (pintype "passive"))
      (node (ref "R14") (pin "2") (pinfunction "2_2") (pintype "passive"))
      (node (ref "R18") (pin "2") (pinfunction "2_2") (pintype "passive"))
      (node (ref "R2") (pin "2") (pinfunction "2_2") (pintype "passive"))
      (node (ref "R20") (pin "2") (pinfunction "2_2") (pintype "passive"))
      (node (ref "R22") (pin "2") (pinfunction "2_2") (pintype "passive"))
      (node (ref "R34") (pin "2") (pinfunction "2_2") (pintype "passive"))
      (node (ref "R36") (pin "2") (pinfunction "2_2") (pintype "passive"))
      (node (ref "R38") (pin "2") (pinfunction "2_2") (pintype "passive"))
      (node (ref "R4") (pin "2") (pinfunction "2_2") (pintype "passive"))
      (node (ref "R42") (pin "2") (pinfunction "2_2") (pintype "passive"))
      (node (ref "R44") (pin "2") (pinfunction "2_2") (pintype "passive"))
      (node (ref "R46") (pin "2") (pinfunction "2_2") (pintype "passive"))
      (node (ref "R50") (pin "2") (pinfunction "2_2") (pintype "passive"))
      (node (ref "R52") (pin "2") (pinfunction "2_2") (pintype "passive"))
      (node (ref "R54") (pin "2") (pinfunction "2_2") (pintype "passive"))
      (node (ref "R6") (pin "2") (pinfunction "2_2") (pintype "passive"))
      (node (ref "R75") (pin "2") (pinfunction "2_2") (pintype "passive"))
      (node (ref "R76") (pin "1") (pinfunction "1_1") (pintype "passive"))
      (node (ref "VAR5A") (pin "3") (pinfunction "3_3") (pintype "passive"))
      (node (ref "VAR5A") (pin "8") (pinfunction "8_8") (pintype "passive"))
      (node (ref "VAR5B") (pin "3") (pinfunction "3_3") (pintype "passive"))
      (node (ref "VAR5B") (pin "8") (pinfunction "8_8") (pintype "passive"))
      (node (ref "VAR5C") (pin "3") (pinfunction "3_3") (pintype "passive"))
      (node (ref "VAR5C") (pin "8") (pinfunction "8_8") (pintype "passive"))
    )
    (net (code "10") (name "/BUS+") (class "Default")
      (node (ref "R71") (pin "2") (pinfunction "2_2") (pintype "passive"))
      (node (ref "R73") (pin "1") (pinfunction "1_1") (pintype "passive"))
      (node (ref "VAR4") (pin "5") (pinfunction "5_5") (pintype "passive"))
    )
    (net (code "11") (name "/GND") (class "Default")
      (node (ref "C35") (pin "P$2") (pinfunction "2_P$2") (pintype "passive"))
      (node (ref "C36") (pin "2") (pinfunction "2_2") (pintype "passive"))
      (node (ref "C37") (pin "P$2") (pinfunction "2_P$2") (pintype "passive"))
      (node (ref "C38") (pin "2") (pinfunction "2_2") (pintype "passive"))
      (node (ref "C39") (pin "2") (pinfunction "2_2") (pintype "passive"))
      (node (ref "C42") (pin "2") (pinfunction "2_2") (pintype "passive"))
      (node (ref "C43") (pin "2") (pinfunction "2_2") (pintype "passive"))
      (node (ref "C44") (pin "2") (pinfunction "2_2") (pintype "passive"))
      (node (ref "C45") (pin "2") (pinfunction "2_2") (pintype "passive"))
      (node (ref "C46") (pin "2") (pinfunction "2_2") (pintype "passive"))
      (node (ref "C47") (pin "2") (pinfunction "2_2") (pintype "passive"))
      (node (ref "C48") (pin "2") (pinfunction "2_2") (pintype "passive"))
      (node (ref "IC1") (pin "8") (pinfunction "VSSA_8") (pintype "power_in"))
      (node (ref "IC3") (pin "1") (pinfunction "GND_1") (pintype "power_in"))
      (node (ref "J2") (pin "3") (pinfunction "3_3") (pintype "passive"))
      (node (ref "J2") (pin "7") (pinfunction "7_7") (pintype "passive"))
      (node (ref "J2") (pin "9") (pinfunction "9_9") (pintype "passive"))
      (node (ref "R67") (pin "1") (pinfunction "1_1") (pintype "passive"))
      (node (ref "R68") (pin "1") (pinfunction "1_1") (pintype "passive"))
      (node (ref "R70") (pin "1") (pinfunction "1_1") (pintype "passive"))
      (node (ref "R85") (pin "1") (pinfunction "1_1") (pintype "passive"))
      (node (ref "SW2") (pin "1") (pinfunction "1_1") (pintype "passive"))
      (node (ref "U$1") (pin "2") (pinfunction "S1_2") (pintype "bidirectional"))
      (node (ref "U$1") (pin "3") (pinfunction "S1_3") (pintype "bidirectional"))
      (node (ref "U$15") (pin "2") (pinfunction "S1_2") (pintype "bidirectional"))
      (node (ref "U$15") (pin "3") (pinfunction "S1_3") (pintype "bidirectional"))
      (node (ref "U$29") (pin "2") (pinfunction "S1_2") (pintype "bidirectional"))
      (node (ref "U$29") (pin "3") (pinfunction "S1_3") (pintype "bidirectional"))
      (node (ref "U$36") (pin "2") (pinfunction "S1_2") (pintype "bidirectional"))
      (node (ref "U$36") (pin "3") (pinfunction "S1_3") (pintype "bidirectional"))
      (node (ref "U$43") (pin "2") (pinfunction "S1_2") (pintype "bidirectional"))
      (node (ref "U$43") (pin "3") (pinfunction "S1_3") (pintype "bidirectional"))
      (node (ref "U$57") (pin "1") (pinfunction "A1_1") (pintype "bidirectional"))
      (node (ref "U$57") (pin "6") (pinfunction "GND_6") (pintype "bidirectional"))
      (node (ref "U$58") (pin "1") (pinfunction "A1_1") (pintype "bidirectional"))
      (node (ref "U$58") (pin "2") (pinfunction "A0_2") (pintype "bidirectional"))
      (node (ref "U$58") (pin "6") (pinfunction "GND_6") (pintype "bidirectional"))
      (node (ref "U$59") (pin "14") (pinfunction "SGND_14") (pintype "bidirectional"))
      (node (ref "U$59") (pin "20") (pinfunction "PGND_20") (pintype "bidirectional"))
      (node (ref "U$59") (pin "25") (pinfunction "PGND_25") (pintype "bidirectional"))
      (node (ref "U$59") (pin "28") (pinfunction "PWM_28") (pintype "bidirectional"))
      (node (ref "U$59") (pin "29") (pinfunction "PGND_29") (pintype "bidirectional"))
      (node (ref "U$59") (pin "4") (pinfunction "PGND_4") (pintype "bidirectional"))
      (node (ref "U$59") (pin "9") (pinfunction "PGND_9") (pintype "bidirectional"))
      (node (ref "U$60") (pin "2") (pinfunction "A_2") (pintype "bidirectional"))
      (node (ref "U$60") (pin "3") (pinfunction "W_3") (pintype "bidirectional"))
      (node (ref "U$60") (pin "4") (pinfunction "VSS_4") (pintype "bidirectional"))
      (node (ref "U$60") (pin "6") (pinfunction "GND_6") (pintype "bidirectional"))
      (node (ref "U$8") (pin "2") (pinfunction "S1_2") (pintype "bidirectional"))
      (node (ref "U$8") (pin "3") (pinfunction "S1_3") (pintype "bidirectional"))
      (node (ref "VAR4") (pin "1") (pinfunction "1_1") (pintype "passive"))
    )
    (net (code "12") (name "/OC1") (class "Default")
      (node (ref "U$1") (pin "5") (pinfunction "G2_5") (pintype "bidirectional"))
      (node (ref "U$3") (pin "2") (pinfunction "OC_2") (pintype "bidirectional"))
    )
    (net (code "13") (name "/OC2") (class "Default")
      (node (ref "U$43") (pin "5") (pinfunction "G2_5") (pintype "bidirectional"))
      (node (ref "U$45") (pin "2") (pinfunction "OC_2") (pintype "bidirectional"))
    )
    (net (code "14") (name "/OC3") (class "Default")
      (node (ref "U$10") (pin "2") (pinfunction "OC_2") (pintype "bidirectional"))
      (node (ref "U$8") (pin "5") (pinfunction "G2_5") (pintype "bidirectional"))
    )
    (net (code "15") (name "/OC4") (class "Default")
      (node (ref "U$36") (pin "5") (pinfunction "G2_5") (pintype "bidirectional"))
      (node (ref "U$38") (pin "2") (pinfunction "OC_2") (pintype "bidirectional"))
    )
    (net (code "16") (name "/OC5") (class "Default")
      (node (ref "U$15") (pin "5") (pinfunction "G2_5") (pintype "bidirectional"))
      (node (ref "U$17") (pin "2") (pinfunction "OC_2") (pintype "bidirectional"))
    )
    (net (code "17") (name "/OC6") (class "Default")
      (node (ref "U$29") (pin "5") (pinfunction "G2_5") (pintype "bidirectional"))
      (node (ref "U$31") (pin "2") (pinfunction "OC_2") (pintype "bidirectional"))
    )
    (net (code "18") (name "/OD1") (class "Default")
      (node (ref "U$1") (pin "4") (pinfunction "G1_4") (pintype "bidirectional"))
      (node (ref "U$3") (pin "1") (pinfunction "OD_1") (pintype "bidirectional"))
    )
    (net (code "19") (name "/OD2") (class "Default")
      (node (ref "U$43") (pin "4") (pinfunction "G1_4") (pintype "bidirectional"))
      (node (ref "U$45") (pin "1") (pinfunction "OD_1") (pintype "bidirectional"))
    )
    (net (code "20") (name "/OD3") (class "Default")
      (node (ref "U$10") (pin "1") (pinfunction "OD_1") (pintype "bidirectional"))
      (node (ref "U$8") (pin "4") (pinfunction "G1_4") (pintype "bidirectional"))
    )
    (net (code "21") (name "/OD4") (class "Default")
      (node (ref "U$36") (pin "4") (pinfunction "G1_4") (pintype "bidirectional"))
      (node (ref "U$38") (pin "1") (pinfunction "OD_1") (pintype "bidirectional"))
    )
    (net (code "22") (name "/OD5") (class "Default")
      (node (ref "U$15") (pin "4") (pinfunction "G1_4") (pintype "bidirectional"))
      (node (ref "U$17") (pin "1") (pinfunction "OD_1") (pintype "bidirectional"))
    )
    (net (code "23") (name "/OD6") (class "Default")
      (node (ref "U$29") (pin "4") (pinfunction "G1_4") (pintype "bidirectional"))
      (node (ref "U$31") (pin "1") (pinfunction "OD_1") (pintype "bidirectional"))
    )
    (net (code "24") (name "/PGOOD") (class "Default")
      (node (ref "IC1") (pin "19") (pinfunction "PB1_19") (pintype "bidirectional"))
      (node (ref "U$59") (pin "10") (pinfunction "PGOOD_10") (pintype "bidirectional"))
    )
    (net (code "25") (name "/RESET") (class "Default")
      (node (ref "IC1") (pin "28") (pinfunction "PB15_28") (pintype "bidirectional"))
      (node (ref "U$60") (pin "7") (pinfunction "RESET_7") (pintype "bidirectional"))
    )
    (net (code "26") (name "/RUN") (class "Default")
      (node (ref "IC1") (pin "27") (pinfunction "PB14_27") (pintype "bidirectional"))
      (node (ref "U$59") (pin "18") (pinfunction "RUN_18") (pintype "bidirectional"))
    )
    (net (code "27") (name "/SCL") (class "Default")
      (node (ref "IC1") (pin "42") (pinfunction "PB6_42") (pintype "bidirectional"))
      (node (ref "U$57") (pin "4") (pinfunction "SCL_4") (pintype "bidirectional"))
      (node (ref "U$58") (pin "4") (pinfunction "SCL_4") (pintype "bidirectional"))
      (node (ref "U$60") (pin "9") (pinfunction "SCL_9") (pintype "bidirectional"))
    )
    (net (code "28") (name "/SCLTM") (class "Default")
      (node (ref "IC1") (pin "21") (pinfunction "PB10_21") (pintype "bidirectional"))
      (node (ref "VAR4") (pin "3") (pinfunction "3_3") (pintype "passive"))
    )
    (net (code "29") (name "/SDA") (class "Default")
      (node (ref "IC1") (pin "43") (pinfunction "PB7_43") (pintype "bidirectional"))
      (node (ref "U$57") (pin "3") (pinfunction "SDA_3") (pintype "bidirectional"))
      (node (ref "U$58") (pin "3") (pinfunction "SDA_3") (pintype "bidirectional"))
      (node (ref "U$60") (pin "8") (pinfunction "SDA_8") (pintype "bidirectional"))
    )
    (net (code "30") (name "/SDATM") (class "Default")
      (node (ref "IC1") (pin "22") (pinfunction "PB11_22") (pintype "bidirectional"))
      (node (ref "VAR4") (pin "2") (pinfunction "2_2") (pintype "passive"))
    )
    (net (code "31") (name "/VBAT") (class "Default")
      (node (ref "IC1") (pin "1") (pinfunction "VBAT_1") (pintype "power_in"))
    )
    (net (code "32") (name "/VDD") (class "Default")
      (node (ref "C48") (pin "1") (pinfunction "1_1") (pintype "passive"))
      (node (ref "D3") (pin "A") (pinfunction "A_A") (pintype "passive"))
      (node (ref "D4") (pin "A") (pinfunction "A_A") (pintype "passive"))
      (node (ref "IC1") (pin "9") (pinfunction "VDDA_9") (pintype "power_in"))
      (node (ref "IC3") (pin "3") (pinfunction "VCC_3") (pintype "input"))
      (node (ref "J2") (pin "1") (pinfunction "1_1") (pintype "passive"))
      (node (ref "R78") (pin "1") (pinfunction "1_1") (pintype "passive"))
      (node (ref "R80") (pin "1") (pinfunction "1_1") (pintype "passive"))
      (node (ref "R81") (pin "1") (pinfunction "1_1") (pintype "passive"))
      (node (ref "R82") (pin "1") (pinfunction "1_1") (pintype "passive"))
      (node (ref "R83") (pin "1") (pinfunction "1_1") (pintype "passive"))
      (node (ref "R84") (pin "2") (pinfunction "2_2") (pintype "passive"))
      (node (ref "U$57") (pin "2") (pinfunction "A0_2") (pintype "bidirectional"))
      (node (ref "U$57") (pin "5") (pinfunction "VCC_5") (pintype "bidirectional"))
      (node (ref "U$58") (pin "5") (pinfunction "VCC_5") (pintype "bidirectional"))
      (node (ref "U$60") (pin "1") (pinfunction "VDD_1") (pintype "bidirectional"))
      (node (ref "U$60") (pin "10") (pinfunction "ADDR_10") (pintype "bidirectional"))
      (node (ref "VAR4") (pin "4") (pinfunction "4_4") (pintype "passive"))
      (node (ref "VAR5A") (pin "4") (pinfunction "4_4") (pintype "passive"))
      (node (ref "VAR5B") (pin "4") (pinfunction "4_4") (pintype "passive"))
      (node (ref "VAR5C") (pin "4") (pinfunction "4_4") (pintype "passive"))
    )
    (net (code "33") (name "Net-(3,3µH-Pad1)") (class "Default")
      (node (ref "3,3µH") (pin "1") (pinfunction "1_1") (pintype "bidirectional"))
      (node (ref "C34") (pin "1") (pinfunction "1_1") (pintype "passive"))
      (node (ref "U$59") (pin "5") (pinfunction "SW2_5") (pintype "bidirectional"))
      (node (ref "U$59") (pin "8") (pinfunction "SW2_8") (pintype "bidirectional"))
    )
    (net (code "34") (name "Net-(3,3µH-Pad2)") (class "Default")
      (node (ref "3,3µH") (pin "2") (pinfunction "2_2") (pintype "bidirectional"))
      (node (ref "C33") (pin "1") (pinfunction "1_1") (pintype "passive"))
      (node (ref "U$59") (pin "21") (pinfunction "SW1_21") (pintype "bidirectional"))
      (node (ref "U$59") (pin "24") (pinfunction "SW1_24") (pintype "bidirectional"))
    )
    (net (code "35") (name "Net-(C35-1)") (class "Default")
      (node (ref "C35") (pin "P$1") (pinfunction "1_P$1") (pintype "passive"))
      (node (ref "R72") (pin "2") (pinfunction "2_2") (pintype "passive"))
      (node (ref "R75") (pin "1") (pinfunction "1_1") (pintype "passive"))
      (node (ref "R77") (pin "1") (pinfunction "1_1") (pintype "passive"))
      (node (ref "U$59") (pin "6") (pinfunction "PVOUT_6") (pintype "bidirectional"))
      (node (ref "U$59") (pin "7") (pinfunction "PVOUT_7") (pintype "bidirectional"))
    )
    (net (code "36") (name "Net-(C36-Pad1)") (class "Default")
      (node (ref "C36") (pin "1") (pinfunction "1_1") (pintype "passive"))
      (node (ref "R69") (pin "2") (pinfunction "2_2") (pintype "passive"))
    )
    (net (code "37") (name "Net-(C37-1)") (class "Default")
      (node (ref "C37") (pin "P$1") (pinfunction "1_P$1") (pintype "passive"))
      (node (ref "R65") (pin "2") (pinfunction "2_2") (pintype "passive"))
      (node (ref "R71") (pin "1") (pinfunction "1_1") (pintype "passive"))
      (node (ref "R74") (pin "1") (pinfunction "1_1") (pintype "passive"))
      (node (ref "U$59") (pin "19") (pinfunction "VIN_19") (pintype "bidirectional"))
      (node (ref "U$59") (pin "22") (pinfunction "PVIN_22") (pintype "bidirectional"))
      (node (ref "U$59") (pin "23") (pinfunction "PVIN_23") (pintype "bidirectional"))
    )
    (net (code "38") (name "Net-(C38-Pad1)") (class "Default")
      (node (ref "C38") (pin "1") (pinfunction "1_1") (pintype "passive"))
      (node (ref "R66") (pin "1") (pinfunction "1_1") (pintype "passive"))
    )
    (net (code "39") (name "Net-(D3-PadK)") (class "Default")
      (node (ref "D3") (pin "K") (pinfunction "K_K") (pintype "passive"))
      (node (ref "R85") (pin "2") (pinfunction "2_2") (pintype "passive"))
    )
    (net (code "40") (name "Net-(D4-PadK)") (class "Default")
      (node (ref "D4") (pin "K") (pinfunction "K_K") (pintype "passive"))
      (node (ref "R86") (pin "1") (pinfunction "1_1") (pintype "passive"))
    )
    (net (code "41") (name "Net-(IC1A-NRST)") (class "Default")
      (node (ref "C43") (pin "1") (pinfunction "1_1") (pintype "passive"))
      (node (ref "IC1") (pin "7") (pinfunction "NRST_7") (pintype "bidirectional"))
      (node (ref "IC3") (pin "2") (pinfunction "/RST_2") (pintype "output"))
      (node (ref "R78") (pin "2") (pinfunction "2_2") (pintype "passive"))
      (node (ref "SJ2") (pin "2") (pinfunction "2_2") (pintype "passive"))
      (node (ref "SW2") (pin "2") (pinfunction "2_2") (pintype "passive"))
    )
    (net (code "42") (name "Net-(IC1A-OSC_IN)") (class "Default")
      (node (ref "C45") (pin "1") (pinfunction "1_1") (pintype "passive"))
      (node (ref "IC1") (pin "5") (pinfunction "OSC_IN_5") (pintype "bidirectional"))
      (node (ref "Q5") (pin "2") (pinfunction "2_2") (pintype "passive"))
      (node (ref "R79") (pin "1") (pinfunction "1_1") (pintype "passive"))
    )
    (net (code "43") (name "Net-(IC1A-OSC_OUT)") (class "Default")
      (node (ref "C44") (pin "1") (pinfunction "1_1") (pintype "passive"))
      (node (ref "IC1") (pin "6") (pinfunction "OSC_OUT_6") (pintype "bidirectional"))
      (node (ref "Q5") (pin "1") (pinfunction "1_1") (pintype "passive"))
      (node (ref "R79") (pin "2") (pinfunction "2_2") (pintype "passive"))
    )
    (net (code "44") (name "Net-(IC1A-PA13)") (class "Default")
      (node (ref "IC1") (pin "34") (pinfunction "PA13_34") (pintype "bidirectional"))
      (node (ref "J2") (pin "2") (pinfunction "2_2") (pintype "passive"))
      (node (ref "R80") (pin "2") (pinfunction "2_2") (pintype "passive"))
    )
    (net (code "45") (name "Net-(IC1A-PA14)") (class "Default")
      (node (ref "IC1") (pin "37") (pinfunction "PA14_37") (pintype "bidirectional"))
      (node (ref "J2") (pin "4") (pinfunction "4_4") (pintype "passive"))
      (node (ref "R81") (pin "2") (pinfunction "2_2") (pintype "passive"))
    )
    (net (code "46") (name "Net-(IC1A-PA15)") (class "Default")
      (node (ref "IC1") (pin "38") (pinfunction "PA15_38") (pintype "bidirectional"))
      (node (ref "J2") (pin "8") (pinfunction "8_8") (pintype "passive"))
      (node (ref "R83") (pin "2") (pinfunction "2_2") (pintype "passive"))
    )
    (net (code "47") (name "Net-(IC1A-PB3)") (class "Default")
      (node (ref "IC1") (pin "39") (pinfunction "PB3_39") (pintype "bidirectional"))
      (node (ref "J2") (pin "6") (pinfunction "6_6") (pintype "passive"))
      (node (ref "R82") (pin "2") (pinfunction "2_2") (pintype "passive"))
    )
    (net (code "48") (name "Net-(IC1A-PB5)") (class "Default")
      (node (ref "IC1") (pin "41") (pinfunction "PB5_41") (pintype "bidirectional"))
      (node (ref "R86") (pin "2") (pinfunction "2_2") (pintype "passive"))
    )
    (net (code "49") (name "Net-(IC1A-PC14)") (class "Default")
      (node (ref "C46") (pin "1") (pinfunction "1_1") (pintype "passive"))
      (node (ref "IC1") (pin "3") (pinfunction "PC14_3") (pintype "bidirectional"))
      (node (ref "Q3") (pin "2") (pinfunction "2_2") (pintype "passive"))
    )
    (net (code "50") (name "Net-(IC1A-PC15)") (class "Default")
      (node (ref "C47") (pin "1") (pinfunction "1_1") (pintype "passive"))
      (node (ref "IC1") (pin "4") (pinfunction "PC15_4") (pintype "bidirectional"))
      (node (ref "Q3") (pin "1") (pinfunction "1_1") (pintype "passive"))
    )
    (net (code "51") (name "Net-(J2-Pad10)") (class "Default")
      (node (ref "J2") (pin "10") (pinfunction "10_10") (pintype "passive"))
      (node (ref "R84") (pin "1") (pinfunction "1_1") (pintype "passive"))
      (node (ref "SJ2") (pin "1") (pinfunction "1_1") (pintype "passive"))
    )
    (net (code "52") (name "Net-(R1-Pad2)") (class "Default")
      (node (ref "R1") (pin "2") (pinfunction "2_2") (pintype "passive"))
      (node (ref "R8") (pin "1") (pinfunction "1_1") (pintype "passive"))
      (node (ref "U$1") (pin "6") (pinfunction "S2_6") (pintype "bidirectional"))
      (node (ref "U$1") (pin "7") (pinfunction "S2_7") (pintype "bidirectional"))
    )
    (net (code "53") (name "Net-(R16-Pad1)") (class "Default")
      (node (ref "R16") (pin "1") (pinfunction "1_1") (pintype "passive"))
      (node (ref "R9") (pin "2") (pinfunction "2_2") (pintype "passive"))
      (node (ref "U$8") (pin "6") (pinfunction "S2_6") (pintype "bidirectional"))
      (node (ref "U$8") (pin "7") (pinfunction "S2_7") (pintype "bidirectional"))
    )
    (net (code "54") (name "Net-(R17-Pad2)") (class "Default")
      (node (ref "R17") (pin "2") (pinfunction "2_2") (pintype "passive"))
      (node (ref "R24") (pin "1") (pinfunction "1_1") (pintype "passive"))
      (node (ref "U$15") (pin "6") (pinfunction "S2_6") (pintype "bidirectional"))
      (node (ref "U$15") (pin "7") (pinfunction "S2_7") (pintype "bidirectional"))
    )
    (net (code "55") (name "Net-(R33-Pad2)") (class "Default")
      (node (ref "R33") (pin "2") (pinfunction "2_2") (pintype "passive"))
      (node (ref "R40") (pin "1") (pinfunction "1_1") (pintype "passive"))
      (node (ref "U$29") (pin "6") (pinfunction "S2_6") (pintype "bidirectional"))
      (node (ref "U$29") (pin "7") (pinfunction "S2_7") (pintype "bidirectional"))
    )
    (net (code "56") (name "Net-(R41-Pad2)") (class "Default")
      (node (ref "R41") (pin "2") (pinfunction "2_2") (pintype "passive"))
      (node (ref "R48") (pin "1") (pinfunction "1_1") (pintype "passive"))
      (node (ref "U$36") (pin "6") (pinfunction "S2_6") (pintype "bidirectional"))
      (node (ref "U$36") (pin "7") (pinfunction "S2_7") (pintype "bidirectional"))
    )
    (net (code "57") (name "Net-(R49-Pad2)") (class "Default")
      (node (ref "R49") (pin "2") (pinfunction "2_2") (pintype "passive"))
      (node (ref "R56") (pin "1") (pinfunction "1_1") (pintype "passive"))
      (node (ref "U$43") (pin "6") (pinfunction "S2_6") (pintype "bidirectional"))
      (node (ref "U$43") (pin "7") (pinfunction "S2_7") (pintype "bidirectional"))
    )
    (net (code "58") (name "Net-(U$3-CS)") (class "Default")
      (node (ref "R1") (pin "1") (pinfunction "1_1") (pintype "passive"))
      (node (ref "U$3") (pin "3") (pinfunction "CS_3") (pintype "bidirectional"))
    )
    (net (code "59") (name "Net-(U$3-VC)") (class "Default")
      (node (ref "C2") (pin "1") (pinfunction "1_1") (pintype "passive"))
      (node (ref "R3") (pin "1") (pinfunction "1_1") (pintype "passive"))
      (node (ref "U$3") (pin "4") (pinfunction "VC_4") (pintype "bidirectional"))
    )
    (net (code "60") (name "Net-(U$3-VDD)") (class "Default")
      (node (ref "C1") (pin "1") (pinfunction "1_1") (pintype "passive"))
      (node (ref "R2") (pin "1") (pinfunction "1_1") (pintype "passive"))
      (node (ref "U$3") (pin "5") (pinfunction "VDD_5") (pintype "bidirectional"))
    )
    (net (code "61") (name "Net-(U$4-OUT)") (class "Default")
      (node (ref "U$4") (pin "6") (pinfunction "OUT_6") (pintype "bidirectional"))
      (node (ref "U$6") (pin "3") (pinfunction "G_3") (pintype "bidirectional"))
    )
    (net (code "62") (name "Net-(U$4-VDD)") (class "Default")
      (node (ref "C3") (pin "1") (pinfunction "1_1") (pintype "passive"))
      (node (ref "R6") (pin "1") (pinfunction "1_1") (pintype "passive"))
      (node (ref "U$4") (pin "2") (pinfunction "VDD_2") (pintype "bidirectional"))
    )
    (net (code "63") (name "Net-(U$4-VSS)") (class "Default")
      (node (ref "C3") (pin "2") (pinfunction "2_2") (pintype "passive"))
      (node (ref "R3") (pin "2") (pinfunction "2_2") (pintype "passive"))
      (node (ref "R5") (pin "2") (pinfunction "2_2") (pintype "passive"))
      (node (ref "R7") (pin "2") (pinfunction "2_2") (pintype "passive"))
      (node (ref "U$4") (pin "3") (pinfunction "VSS_3") (pintype "bidirectional"))
      (node (ref "U$6") (pin "1") (pinfunction "D_1") (pintype "bidirectional"))
      (node (ref "VAR5A") (pin "7") (pinfunction "7_7") (pintype "passive"))
    )
    (net (code "64") (name "Net-(U$5-OUT)") (class "Default")
      (node (ref "U$5") (pin "6") (pinfunction "OUT_6") (pintype "bidirectional"))
      (node (ref "U$7") (pin "3") (pinfunction "G_3") (pintype "bidirectional"))
    )
    (net (code "65") (name "Net-(U$5-VDD)") (class "Default")
      (node (ref "C4") (pin "1") (pinfunction "1_1") (pintype "passive"))
      (node (ref "R7") (pin "1") (pinfunction "1_1") (pintype "passive"))
      (node (ref "U$5") (pin "2") (pinfunction "VDD_2") (pintype "bidirectional"))
    )
    (net (code "66") (name "Net-(U$6-S)") (class "Default")
      (node (ref "R4") (pin "1") (pinfunction "1_1") (pintype "passive"))
      (node (ref "U$6") (pin "2") (pinfunction "S_2") (pintype "bidirectional"))
    )
    (net (code "67") (name "Net-(U$7-S)") (class "Default")
      (node (ref "R5") (pin "1") (pinfunction "1_1") (pintype "passive"))
      (node (ref "U$7") (pin "2") (pinfunction "S_2") (pintype "bidirectional"))
    )
    (net (code "68") (name "Net-(U$10-CS)") (class "Default")
      (node (ref "R9") (pin "1") (pinfunction "1_1") (pintype "passive"))
      (node (ref "U$10") (pin "3") (pinfunction "CS_3") (pintype "bidirectional"))
    )
    (net (code "69") (name "Net-(U$10-VC)") (class "Default")
      (node (ref "C6") (pin "1") (pinfunction "1_1") (pintype "passive"))
      (node (ref "R11") (pin "1") (pinfunction "1_1") (pintype "passive"))
      (node (ref "U$10") (pin "4") (pinfunction "VC_4") (pintype "bidirectional"))
    )
    (net (code "70") (name "Net-(U$10-VDD)") (class "Default")
      (node (ref "C5") (pin "1") (pinfunction "1_1") (pintype "passive"))
      (node (ref "R10") (pin "1") (pinfunction "1_1") (pintype "passive"))
      (node (ref "U$10") (pin "5") (pinfunction "VDD_5") (pintype "bidirectional"))
    )
    (net (code "71") (name "Net-(U$11-OUT)") (class "Default")
      (node (ref "U$11") (pin "6") (pinfunction "OUT_6") (pintype "bidirectional"))
      (node (ref "U$13") (pin "3") (pinfunction "G_3") (pintype "bidirectional"))
    )
    (net (code "72") (name "Net-(U$11-VDD)") (class "Default")
      (node (ref "C7") (pin "1") (pinfunction "1_1") (pintype "passive"))
      (node (ref "R14") (pin "1") (pinfunction "1_1") (pintype "passive"))
      (node (ref "U$11") (pin "2") (pinfunction "VDD_2") (pintype "bidirectional"))
    )
    (net (code "73") (name "Net-(U$11-VSS)") (class "Default")
      (node (ref "C7") (pin "2") (pinfunction "2_2") (pintype "passive"))
      (node (ref "R11") (pin "2") (pinfunction "2_2") (pintype "passive"))
      (node (ref "R13") (pin "2") (pinfunction "2_2") (pintype "passive"))
      (node (ref "R15") (pin "2") (pinfunction "2_2") (pintype "passive"))
      (node (ref "U$11") (pin "3") (pinfunction "VSS_3") (pintype "bidirectional"))
      (node (ref "U$13") (pin "1") (pinfunction "D_1") (pintype "bidirectional"))
      (node (ref "VAR5B") (pin "7") (pinfunction "7_7") (pintype "passive"))
    )
    (net (code "74") (name "Net-(U$12-OUT)") (class "Default")
      (node (ref "U$12") (pin "6") (pinfunction "OUT_6") (pintype "bidirectional"))
      (node (ref "U$14") (pin "3") (pinfunction "G_3") (pintype "bidirectional"))
    )
    (net (code "75") (name "Net-(U$12-VDD)") (class "Default")
      (node (ref "C8") (pin "1") (pinfunction "1_1") (pintype "passive"))
      (node (ref "R15") (pin "1") (pinfunction "1_1") (pintype "passive"))
      (node (ref "U$12") (pin "2") (pinfunction "VDD_2") (pintype "bidirectional"))
    )
    (net (code "76") (name "Net-(U$13-S)") (class "Default")
      (node (ref "R12") (pin "1") (pinfunction "1_1") (pintype "passive"))
      (node (ref "U$13") (pin "2") (pinfunction "S_2") (pintype "bidirectional"))
    )
    (net (code "77") (name "Net-(U$14-S)") (class "Default")
      (node (ref "R13") (pin "1") (pinfunction "1_1") (pintype "passive"))
      (node (ref "U$14") (pin "2") (pinfunction "S_2") (pintype "bidirectional"))
    )
    (net (code "78") (name "Net-(U$17-CS)") (class "Default")
      (node (ref "R17") (pin "1") (pinfunction "1_1") (pintype "passive"))
      (node (ref "U$17") (pin "3") (pinfunction "CS_3") (pintype "bidirectional"))
    )
    (net (code "79") (name "Net-(U$17-VC)") (class "Default")
      (node (ref "C10") (pin "1") (pinfunction "1_1") (pintype "passive"))
      (node (ref "R19") (pin "1") (pinfunction "1_1") (pintype "passive"))
      (node (ref "U$17") (pin "4") (pinfunction "VC_4") (pintype "bidirectional"))
    )
    (net (code "80") (name "Net-(U$17-VDD)") (class "Default")
      (node (ref "C9") (pin "1") (pinfunction "1_1") (pintype "passive"))
      (node (ref "R18") (pin "1") (pinfunction "1_1") (pintype "passive"))
      (node (ref "U$17") (pin "5") (pinfunction "VDD_5") (pintype "bidirectional"))
    )
    (net (code "81") (name "Net-(U$18-OUT)") (class "Default")
      (node (ref "U$18") (pin "6") (pinfunction "OUT_6") (pintype "bidirectional"))
      (node (ref "U$20") (pin "3") (pinfunction "G_3") (pintype "bidirectional"))
    )
    (net (code "82") (name "Net-(U$18-VDD)") (class "Default")
      (node (ref "C11") (pin "1") (pinfunction "1_1") (pintype "passive"))
      (node (ref "R22") (pin "1") (pinfunction "1_1") (pintype "passive"))
      (node (ref "U$18") (pin "2") (pinfunction "VDD_2") (pintype "bidirectional"))
    )
    (net (code "83") (name "Net-(U$18-VSS)") (class "Default")
      (node (ref "C11") (pin "2") (pinfunction "2_2") (pintype "passive"))
      (node (ref "R19") (pin "2") (pinfunction "2_2") (pintype "passive"))
      (node (ref "R21") (pin "2") (pinfunction "2_2") (pintype "passive"))
      (node (ref "R23") (pin "2") (pinfunction "2_2") (pintype "passive"))
      (node (ref "U$18") (pin "3") (pinfunction "VSS_3") (pintype "bidirectional"))
      (node (ref "U$20") (pin "1") (pinfunction "D_1") (pintype "bidirectional"))
      (node (ref "VAR5C") (pin "7") (pinfunction "7_7") (pintype "passive"))
    )
    (net (code "84") (name "Net-(U$19-OUT)") (class "Default")
      (node (ref "U$19") (pin "6") (pinfunction "OUT_6") (pintype "bidirectional"))
      (node (ref "U$21") (pin "3") (pinfunction "G_3") (pintype "bidirectional"))
    )
    (net (code "85") (name "Net-(U$19-VDD)") (class "Default")
      (node (ref "C12") (pin "1") (pinfunction "1_1") (pintype "passive"))
      (node (ref "R23") (pin "1") (pinfunction "1_1") (pintype "passive"))
      (node (ref "U$19") (pin "2") (pinfunction "VDD_2") (pintype "bidirectional"))
    )
    (net (code "86") (name "Net-(U$20-S)") (class "Default")
      (node (ref "R20") (pin "1") (pinfunction "1_1") (pintype "passive"))
      (node (ref "U$20") (pin "2") (pinfunction "S_2") (pintype "bidirectional"))
    )
    (net (code "87") (name "Net-(U$21-S)") (class "Default")
      (node (ref "R21") (pin "1") (pinfunction "1_1") (pintype "passive"))
      (node (ref "U$21") (pin "2") (pinfunction "S_2") (pintype "bidirectional"))
    )
    (net (code "88") (name "Net-(U$31-CS)") (class "Default")
      (node (ref "R33") (pin "1") (pinfunction "1_1") (pintype "passive"))
      (node (ref "U$31") (pin "3") (pinfunction "CS_3") (pintype "bidirectional"))
    )
    (net (code "89") (name "Net-(U$31-VC)") (class "Default")
      (node (ref "C18") (pin "1") (pinfunction "1_1") (pintype "passive"))
      (node (ref "R35") (pin "1") (pinfunction "1_1") (pintype "passive"))
      (node (ref "U$31") (pin "4") (pinfunction "VC_4") (pintype "bidirectional"))
    )
    (net (code "90") (name "Net-(U$31-VDD)") (class "Default")
      (node (ref "C17") (pin "1") (pinfunction "1_1") (pintype "passive"))
      (node (ref "R34") (pin "1") (pinfunction "1_1") (pintype "passive"))
      (node (ref "U$31") (pin "5") (pinfunction "VDD_5") (pintype "bidirectional"))
    )
    (net (code "91") (name "Net-(U$32-OUT)") (class "Default")
      (node (ref "U$32") (pin "6") (pinfunction "OUT_6") (pintype "bidirectional"))
      (node (ref "U$34") (pin "3") (pinfunction "G_3") (pintype "bidirectional"))
    )
    (net (code "92") (name "Net-(U$32-VDD)") (class "Default")
      (node (ref "C19") (pin "1") (pinfunction "1_1") (pintype "passive"))
      (node (ref "R38") (pin "1") (pinfunction "1_1") (pintype "passive"))
      (node (ref "U$32") (pin "2") (pinfunction "VDD_2") (pintype "bidirectional"))
    )
    (net (code "93") (name "Net-(U$32-VSS)") (class "Default")
      (node (ref "C19") (pin "2") (pinfunction "2_2") (pintype "passive"))
      (node (ref "R35") (pin "2") (pinfunction "2_2") (pintype "passive"))
      (node (ref "R37") (pin "2") (pinfunction "2_2") (pintype "passive"))
      (node (ref "R39") (pin "2") (pinfunction "2_2") (pintype "passive"))
      (node (ref "U$32") (pin "3") (pinfunction "VSS_3") (pintype "bidirectional"))
      (node (ref "U$34") (pin "1") (pinfunction "D_1") (pintype "bidirectional"))
      (node (ref "VAR5C") (pin "2") (pinfunction "2_2") (pintype "passive"))
    )
    (net (code "94") (name "Net-(U$33-OUT)") (class "Default")
      (node (ref "U$33") (pin "6") (pinfunction "OUT_6") (pintype "bidirectional"))
      (node (ref "U$35") (pin "3") (pinfunction "G_3") (pintype "bidirectional"))
    )
    (net (code "95") (name "Net-(U$33-VDD)") (class "Default")
      (node (ref "C20") (pin "1") (pinfunction "1_1") (pintype "passive"))
      (node (ref "R39") (pin "1") (pinfunction "1_1") (pintype "passive"))
      (node (ref "U$33") (pin "2") (pinfunction "VDD_2") (pintype "bidirectional"))
    )
    (net (code "96") (name "Net-(U$34-S)") (class "Default")
      (node (ref "R36") (pin "1") (pinfunction "1_1") (pintype "passive"))
      (node (ref "U$34") (pin "2") (pinfunction "S_2") (pintype "bidirectional"))
    )
    (net (code "97") (name "Net-(U$35-S)") (class "Default")
      (node (ref "R37") (pin "1") (pinfunction "1_1") (pintype "passive"))
      (node (ref "U$35") (pin "2") (pinfunction "S_2") (pintype "bidirectional"))
    )
    (net (code "98") (name "Net-(U$38-CS)") (class "Default")
      (node (ref "R41") (pin "1") (pinfunction "1_1") (pintype "passive"))
      (node (ref "U$38") (pin "3") (pinfunction "CS_3") (pintype "bidirectional"))
    )
    (net (code "99") (name "Net-(U$38-VC)") (class "Default")
      (node (ref "C22") (pin "1") (pinfunction "1_1") (pintype "passive"))
      (node (ref "R43") (pin "1") (pinfunction "1_1") (pintype "passive"))
      (node (ref "U$38") (pin "4") (pinfunction "VC_4") (pintype "bidirectional"))
    )
    (net (code "100") (name "Net-(U$38-VDD)") (class "Default")
      (node (ref "C21") (pin "1") (pinfunction "1_1") (pintype "passive"))
      (node (ref "R42") (pin "1") (pinfunction "1_1") (pintype "passive"))
      (node (ref "U$38") (pin "5") (pinfunction "VDD_5") (pintype "bidirectional"))
    )
    (net (code "101") (name "Net-(U$39-OUT)") (class "Default")
      (node (ref "U$39") (pin "6") (pinfunction "OUT_6") (pintype "bidirectional"))
      (node (ref "U$41") (pin "3") (pinfunction "G_3") (pintype "bidirectional"))
    )
    (net (code "102") (name "Net-(U$39-VDD)") (class "Default")
      (node (ref "C23") (pin "1") (pinfunction "1_1") (pintype "passive"))
      (node (ref "R46") (pin "1") (pinfunction "1_1") (pintype "passive"))
      (node (ref "U$39") (pin "2") (pinfunction "VDD_2") (pintype "bidirectional"))
    )
    (net (code "103") (name "Net-(U$39-VSS)") (class "Default")
      (node (ref "C23") (pin "2") (pinfunction "2_2") (pintype "passive"))
      (node (ref "R43") (pin "2") (pinfunction "2_2") (pintype "passive"))
      (node (ref "R45") (pin "2") (pinfunction "2_2") (pintype "passive"))
      (node (ref "R47") (pin "2") (pinfunction "2_2") (pintype "passive"))
      (node (ref "U$39") (pin "3") (pinfunction "VSS_3") (pintype "bidirectional"))
      (node (ref "U$41") (pin "1") (pinfunction "D_1") (pintype "bidirectional"))
      (node (ref "VAR5B") (pin "2") (pinfunction "2_2") (pintype "passive"))
    )
    (net (code "104") (name "Net-(U$40-OUT)") (class "Default")
      (node (ref "U$40") (pin "6") (pinfunction "OUT_6") (pintype "bidirectional"))
      (node (ref "U$42") (pin "3") (pinfunction "G_3") (pintype "bidirectional"))
    )
    (net (code "105") (name "Net-(U$40-VDD)") (class "Default")
      (node (ref "C24") (pin "1") (pinfunction "1_1") (pintype "passive"))
      (node (ref "R47") (pin "1") (pinfunction "1_1") (pintype "passive"))
      (node (ref "U$40") (pin "2") (pinfunction "VDD_2") (pintype "bidirectional"))
    )
    (net (code "106") (name "Net-(U$41-S)") (class "Default")
      (node (ref "R44") (pin "1") (pinfunction "1_1") (pintype "passive"))
      (node (ref "U$41") (pin "2") (pinfunction "S_2") (pintype "bidirectional"))
    )
    (net (code "107") (name "Net-(U$42-S)") (class "Default")
      (node (ref "R45") (pin "1") (pinfunction "1_1") (pintype "passive"))
      (node (ref "U$42") (pin "2") (pinfunction "S_2") (pintype "bidirectional"))
    )
    (net (code "108") (name "Net-(U$45-CS)") (class "Default")
      (node (ref "R49") (pin "1") (pinfunction "1_1") (pintype "passive"))
      (node (ref "U$45") (pin "3") (pinfunction "CS_3") (pintype "bidirectional"))
    )
    (net (code "109") (name "Net-(U$45-VC)") (class "Default")
      (node (ref "C26") (pin "1") (pinfunction "1_1") (pintype "passive"))
      (node (ref "R51") (pin "1") (pinfunction "1_1") (pintype "passive"))
      (node (ref "U$45") (pin "4") (pinfunction "VC_4") (pintype "bidirectional"))
    )
    (net (code "110") (name "Net-(U$45-VDD)") (class "Default")
      (node (ref "C25") (pin "1") (pinfunction "1_1") (pintype "passive"))
      (node (ref "R50") (pin "1") (pinfunction "1_1") (pintype "passive"))
      (node (ref "U$45") (pin "5") (pinfunction "VDD_5") (pintype "bidirectional"))
    )
    (net (code "111") (name "Net-(U$46-OUT)") (class "Default")
      (node (ref "U$46") (pin "6") (pinfunction "OUT_6") (pintype "bidirectional"))
      (node (ref "U$48") (pin "3") (pinfunction "G_3") (pintype "bidirectional"))
    )
    (net (code "112") (name "Net-(U$46-VDD)") (class "Default")
      (node (ref "C27") (pin "1") (pinfunction "1_1") (pintype "passive"))
      (node (ref "R54") (pin "1") (pinfunction "1_1") (pintype "passive"))
      (node (ref "U$46") (pin "2") (pinfunction "VDD_2") (pintype "bidirectional"))
    )
    (net (code "113") (name "Net-(U$46-VSS)") (class "Default")
      (node (ref "C27") (pin "2") (pinfunction "2_2") (pintype "passive"))
      (node (ref "R51") (pin "2") (pinfunction "2_2") (pintype "passive"))
      (node (ref "R53") (pin "2") (pinfunction "2_2") (pintype "passive"))
      (node (ref "R55") (pin "2") (pinfunction "2_2") (pintype "passive"))
      (node (ref "U$46") (pin "3") (pinfunction "VSS_3") (pintype "bidirectional"))
      (node (ref "U$48") (pin "1") (pinfunction "D_1") (pintype "bidirectional"))
      (node (ref "VAR5A") (pin "2") (pinfunction "2_2") (pintype "passive"))
    )
    (net (code "114") (name "Net-(U$47-OUT)") (class "Default")
      (node (ref "U$47") (pin "6") (pinfunction "OUT_6") (pintype "bidirectional"))
      (node (ref "U$49") (pin "3") (pinfunction "G_3") (pintype "bidirectional"))
    )
    (net (code "115") (name "Net-(U$47-VDD)") (class "Default")
      (node (ref "C28") (pin "1") (pinfunction "1_1") (pintype "passive"))
      (node (ref "R55") (pin "1") (pinfunction "1_1") (pintype "passive"))
      (node (ref "U$47") (pin "2") (pinfunction "VDD_2") (pintype "bidirectional"))
    )
    (net (code "116") (name "Net-(U$48-S)") (class "Default")
      (node (ref "R52") (pin "1") (pinfunction "1_1") (pintype "passive"))
      (node (ref "U$48") (pin "2") (pinfunction "S_2") (pintype "bidirectional"))
    )
    (net (code "117") (name "Net-(U$49-S)") (class "Default")
      (node (ref "R53") (pin "1") (pinfunction "1_1") (pintype "passive"))
      (node (ref "U$49") (pin "2") (pinfunction "S_2") (pintype "bidirectional"))
    )
    (net (code "118") (name "Net-(U$57-IN+)") (class "Default")
      (node (ref "C41") (pin "1") (pinfunction "1_1") (pintype "passive"))
      (node (ref "R76") (pin "2") (pinfunction "2_2") (pintype "passive"))
      (node (ref "U$57") (pin "8") (pinfunction "IN+_8") (pintype "bidirectional"))
    )
    (net (code "119") (name "Net-(U$57-IN-)") (class "Default")
      (node (ref "C41") (pin "2") (pinfunction "2_2") (pintype "passive"))
      (node (ref "R77") (pin "2") (pinfunction "2_2") (pintype "passive"))
      (node (ref "U$57") (pin "7") (pinfunction "IN-_7") (pintype "bidirectional"))
    )
    (net (code "120") (name "Net-(U$58-IN+)") (class "Default")
      (node (ref "C40") (pin "1") (pinfunction "1_1") (pintype "passive"))
      (node (ref "R73") (pin "2") (pinfunction "2_2") (pintype "passive"))
      (node (ref "U$58") (pin "8") (pinfunction "IN+_8") (pintype "bidirectional"))
    )
    (net (code "121") (name "Net-(U$58-IN-)") (class "Default")
      (node (ref "C40") (pin "2") (pinfunction "2_2") (pintype "passive"))
      (node (ref "R74") (pin "2") (pinfunction "2_2") (pintype "passive"))
      (node (ref "U$58") (pin "7") (pinfunction "IN-_7") (pintype "bidirectional"))
    )
    (net (code "122") (name "Net-(U$59-BST1)") (class "Default")
      (node (ref "C33") (pin "2") (pinfunction "2_2") (pintype "passive"))
      (node (ref "U$59") (pin "26") (pinfunction "BST1_26") (pintype "bidirectional"))
    )
    (net (code "123") (name "Net-(U$59-BST2)") (class "Default")
      (node (ref "C34") (pin "2") (pinfunction "2_2") (pintype "passive"))
      (node (ref "U$59") (pin "3") (pinfunction "BST2_3") (pintype "bidirectional"))
    )
    (net (code "124") (name "Net-(U$59-FB)") (class "Default")
      (node (ref "R70") (pin "2") (pinfunction "2_2") (pintype "passive"))
      (node (ref "R72") (pin "1") (pinfunction "1_1") (pintype "passive"))
      (node (ref "U$59") (pin "12") (pinfunction "FB_12") (pintype "bidirectional"))
    )
    (net (code "125") (name "Net-(U$59-MPPC)") (class "Default")
      (node (ref "R65") (pin "1") (pinfunction "1_1") (pintype "passive"))
      (node (ref "R66") (pin "2") (pinfunction "2_2") (pintype "passive"))
      (node (ref "R67") (pin "2") (pinfunction "2_2") (pintype "passive"))
      (node (ref "U$59") (pin "15") (pinfunction "MPPC_15") (pintype "bidirectional"))
    )
    (net (code "126") (name "Net-(U$59-RT)") (class "Default")
      (node (ref "R68") (pin "2") (pinfunction "2_2") (pintype "passive"))
      (node (ref "U$59") (pin "17") (pinfunction "RT_17") (pintype "bidirectional"))
    )
    (net (code "127") (name "Net-(U$59-SVCC)") (class "Default")
      (node (ref "C39") (pin "1") (pinfunction "1_1") (pintype "passive"))
      (node (ref "U$59") (pin "11") (pinfunction "SVCC_11") (pintype "bidirectional"))
      (node (ref "U$59") (pin "16") (pinfunction "VCC_16") (pintype "bidirectional"))
    )
    (net (code "128") (name "Net-(U$59-VC)") (class "Default")
      (node (ref "R69") (pin "1") (pinfunction "1_1") (pintype "passive"))
      (node (ref "U$59") (pin "13") (pinfunction "VC_13") (pintype "bidirectional"))
    )
    (net (code "129") (name "Net-(U$60-CAP)") (class "Default")
      (node (ref "C42") (pin "1") (pinfunction "1_1") (pintype "passive"))
      (node (ref "U$60") (pin "5") (pinfunction "CAP_5") (pintype "bidirectional"))
    )
    (net (code "130") (name "unconnected-(IC1A-BOOT0-Pad44)") (class "Default")
      (node (ref "IC1") (pin "44") (pinfunction "BOOT0_44") (pintype "input"))
    )
    (net (code "131") (name "unconnected-(IC1A-PA0-WKUP-Pad10)") (class "Default")
      (node (ref "IC1") (pin "10") (pinfunction "PA0-WKUP_10") (pintype "bidirectional"))
    )
    (net (code "132") (name "unconnected-(IC1A-PA1-Pad11)") (class "Default")
      (node (ref "IC1") (pin "11") (pinfunction "PA1_11") (pintype "bidirectional"))
    )
    (net (code "133") (name "unconnected-(IC1A-PA2-Pad12)") (class "Default")
      (node (ref "IC1") (pin "12") (pinfunction "PA2_12") (pintype "bidirectional"))
    )
    (net (code "134") (name "unconnected-(IC1A-PA3-Pad13)") (class "Default")
      (node (ref "IC1") (pin "13") (pinfunction "PA3_13") (pintype "bidirectional"))
    )
    (net (code "135") (name "unconnected-(IC1A-PA4-Pad14)") (class "Default")
      (node (ref "IC1") (pin "14") (pinfunction "PA4_14") (pintype "bidirectional"))
    )
    (net (code "136") (name "unconnected-(IC1A-PA5-Pad15)") (class "Default")
      (node (ref "IC1") (pin "15") (pinfunction "PA5_15") (pintype "bidirectional"))
    )
    (net (code "137") (name "unconnected-(IC1A-PA6-Pad16)") (class "Default")
      (node (ref "IC1") (pin "16") (pinfunction "PA6_16") (pintype "bidirectional"))
    )
    (net (code "138") (name "unconnected-(IC1A-PA7-Pad17)") (class "Default")
      (node (ref "IC1") (pin "17") (pinfunction "PA7_17") (pintype "bidirectional"))
    )
    (net (code "139") (name "unconnected-(IC1A-PA8-Pad29)") (class "Default")
      (node (ref "IC1") (pin "29") (pinfunction "PA8_29") (pintype "bidirectional"))
    )
    (net (code "140") (name "unconnected-(IC1A-PA9-Pad30)") (class "Default")
      (node (ref "IC1") (pin "30") (pinfunction "PA9_30") (pintype "bidirectional"))
    )
    (net (code "141") (name "unconnected-(IC1A-PA10-Pad31)") (class "Default")
      (node (ref "IC1") (pin "31") (pinfunction "PA10_31") (pintype "bidirectional"))
    )
    (net (code "142") (name "unconnected-(IC1A-PA11-Pad32)") (class "Default")
      (node (ref "IC1") (pin "32") (pinfunction "PA11_32") (pintype "bidirectional"))
    )
    (net (code "143") (name "unconnected-(IC1A-PA12-Pad33)") (class "Default")
      (node (ref "IC1") (pin "33") (pinfunction "PA12_33") (pintype "bidirectional"))
    )
    (net (code "144") (name "unconnected-(IC1A-PB2-Pad20)") (class "Default")
      (node (ref "IC1") (pin "20") (pinfunction "PB2_20") (pintype "bidirectional"))
    )
    (net (code "145") (name "unconnected-(IC1A-PB4-Pad40)") (class "Default")
      (node (ref "IC1") (pin "40") (pinfunction "PB4_40") (pintype "bidirectional"))
    )
    (net (code "146") (name "unconnected-(IC1A-PB8-Pad45)") (class "Default")
      (node (ref "IC1") (pin "45") (pinfunction "PB8_45") (pintype "bidirectional"))
    )
    (net (code "147") (name "unconnected-(IC1A-PB9-Pad46)") (class "Default")
      (node (ref "IC1") (pin "46") (pinfunction "PB9_46") (pintype "bidirectional"))
    )
    (net (code "148") (name "unconnected-(IC1A-PB12-Pad25)") (class "Default")
      (node (ref "IC1") (pin "25") (pinfunction "PB12_25") (pintype "bidirectional"))
    )
    (net (code "149") (name "unconnected-(IC1A-PB13-Pad26)") (class "Default")
      (node (ref "IC1") (pin "26") (pinfunction "PB13_26") (pintype "bidirectional"))
    )
    (net (code "150") (name "unconnected-(IC1A-PC13-Pad2)") (class "Default")
      (node (ref "IC1") (pin "2") (pinfunction "PC13_2") (pintype "bidirectional"))
    )
    (net (code "151") (name "unconnected-(J2-Pad5)") (class "Default")
      (node (ref "J2") (pin "5") (pinfunction "5_5") (pintype "passive"))
    )
  )
)
